# SCH_LED-Matrix-Halflife_2026-10-07.net
KiCad netlist of a schematic drawn in EasyEDA
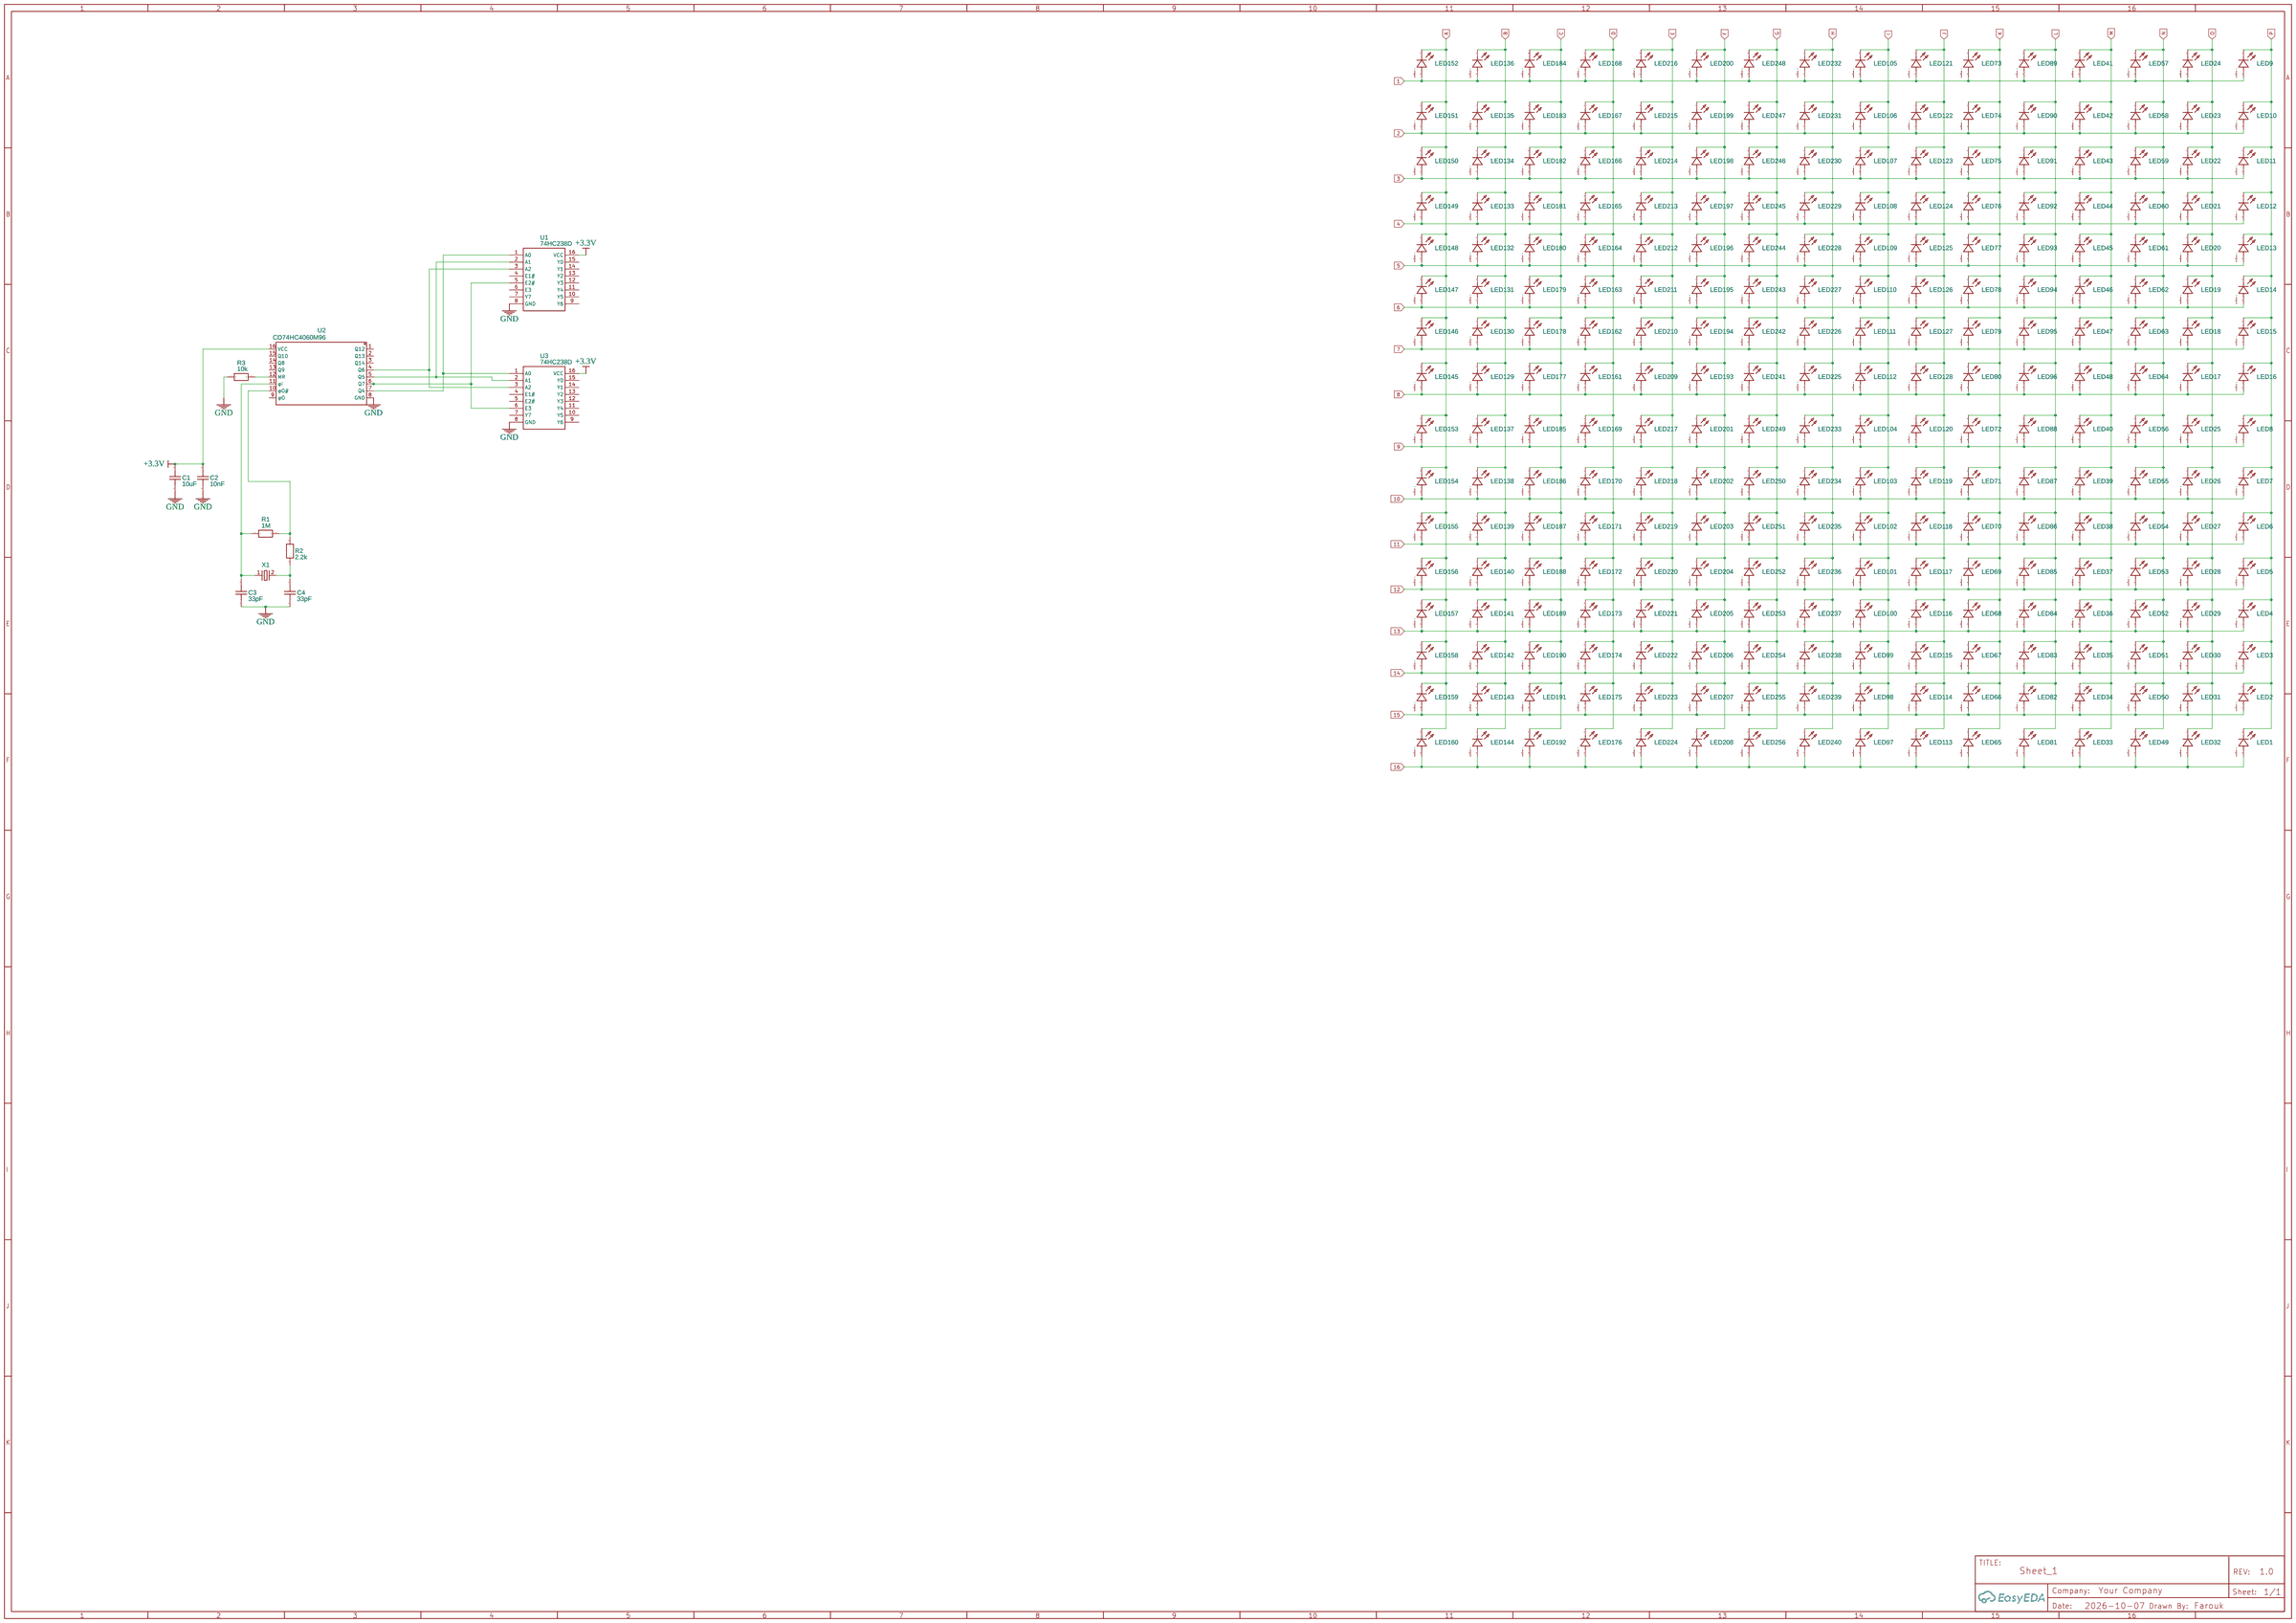
[diagram p0: schematic sheet]

(export (version "E")
  (design (tool "Eeschema 10.0.6"))
  (components
    (comp (ref "C1")
      (value "10uF")
      (fields
        (field (name "Manufacturer Part") "CC1210Y5V16V106ZN")
        (field (name "Manufacturer") "TORCH(火炬)")
      )
      (libsource (lib "") (part "CC1210Y5V16V106ZN"))
    )
    (comp (ref "C2")
      (value "10nF")
      (fields
        (field (name "Manufacturer Part") "CSA0805C0G103J500MT")
        (field (name "Manufacturer") "HRE(芯声)")
      )
      (libsource (lib "") (part "CSA0805C0G103J500MT"))
    )
    (comp (ref "C3")
      (value "33pF")
      (fields (field (name "Manufacturer Part") "600F330JT250XT") (field (name "Manufacturer") "Kyocera AVX"))
      (libsource (lib "") (part "600F330JT250XT"))
    )
    (comp (ref "C4")
      (value "33pF")
      (fields (field (name "Manufacturer Part") "600F330JT250XT") (field (name "Manufacturer") "Kyocera AVX"))
      (libsource (lib "") (part "600F330JT250XT"))
    )
    (comp (ref "LED1")
      (value "HL-A-5730D34WY-S1-08-CZ(LY)")
      (fields (field (name "Manufacturer") "HONGLITRONIC(鸿利光电)"))
      (libsource (lib "") (part "HL-A-5730D34WY-S1-08-CZ(LY)"))
    )
    (comp (ref "LED2")
      (value "HL-A-5730D34WY-S1-08-CZ(LY)")
      (fields (field (name "Manufacturer") "HONGLITRONIC(鸿利光电)"))
      (libsource (lib "") (part "HL-A-5730D34WY-S1-08-CZ(LY)"))
    )
    (comp (ref "LED3")
      (value "HL-A-5730D34WY-S1-08-CZ(LY)")
      (fields (field (name "Manufacturer") "HONGLITRONIC(鸿利光电)"))
      (libsource (lib "") (part "HL-A-5730D34WY-S1-08-CZ(LY)"))
    )
    (comp (ref "LED4")
      (value "HL-A-5730D34WY-S1-08-CZ(LY)")
      (fields (field (name "Manufacturer") "HONGLITRONIC(鸿利光电)"))
      (libsource (lib "") (part "HL-A-5730D34WY-S1-08-CZ(LY)"))
    )
    (comp (ref "LED5")
      (value "HL-A-5730D34WY-S1-08-CZ(LY)")
      (fields (field (name "Manufacturer") "HONGLITRONIC(鸿利光电)"))
      (libsource (lib "") (part "HL-A-5730D34WY-S1-08-CZ(LY)"))
    )
    (comp (ref "LED6")
      (value "HL-A-5730D34WY-S1-08-CZ(LY)")
      (fields (field (name "Manufacturer") "HONGLITRONIC(鸿利光电)"))
      (libsource (lib "") (part "HL-A-5730D34WY-S1-08-CZ(LY)"))
    )
    (comp (ref "LED7")
      (value "HL-A-5730D34WY-S1-08-CZ(LY)")
      (fields (field (name "Manufacturer") "HONGLITRONIC(鸿利光电)"))
      (libsource (lib "") (part "HL-A-5730D34WY-S1-08-CZ(LY)"))
    )
    (comp (ref "LED8")
      (value "HL-A-5730D34WY-S1-08-CZ(LY)")
      (fields (field (name "Manufacturer") "HONGLITRONIC(鸿利光电)"))
      (libsource (lib "") (part "HL-A-5730D34WY-S1-08-CZ(LY)"))
    )
    (comp (ref "LED9")
      (value "HL-A-5730D34WY-S1-08-CZ(LY)")
      (fields (field (name "Manufacturer") "HONGLITRONIC(鸿利光电)"))
      (libsource (lib "") (part "HL-A-5730D34WY-S1-08-CZ(LY)"))
    )
    (comp (ref "LED10")
      (value "HL-A-5730D34WY-S1-08-CZ(LY)")
      (fields (field (name "Manufacturer") "HONGLITRONIC(鸿利光电)"))
      (libsource (lib "") (part "HL-A-5730D34WY-S1-08-CZ(LY)"))
    )
    (comp (ref "LED11")
      (value "HL-A-5730D34WY-S1-08-CZ(LY)")
      (fields (field (name "Manufacturer") "HONGLITRONIC(鸿利光电)"))
      (libsource (lib "") (part "HL-A-5730D34WY-S1-08-CZ(LY)"))
    )
    (comp (ref "LED12")
      (value "HL-A-5730D34WY-S1-08-CZ(LY)")
      (fields (field (name "Manufacturer") "HONGLITRONIC(鸿利光电)"))
      (libsource (lib "") (part "HL-A-5730D34WY-S1-08-CZ(LY)"))
    )
    (comp (ref "LED13")
      (value "HL-A-5730D34WY-S1-08-CZ(LY)")
      (fields (field (name "Manufacturer") "HONGLITRONIC(鸿利光电)"))
      (libsource (lib "") (part "HL-A-5730D34WY-S1-08-CZ(LY)"))
    )
    (comp (ref "LED14")
      (value "HL-A-5730D34WY-S1-08-CZ(LY)")
      (fields (field (name "Manufacturer") "HONGLITRONIC(鸿利光电)"))
      (libsource (lib "") (part "HL-A-5730D34WY-S1-08-CZ(LY)"))
    )
    (comp (ref "LED15")
      (value "HL-A-5730D34WY-S1-08-CZ(LY)")
      (fields (field (name "Manufacturer") "HONGLITRONIC(鸿利光电)"))
      (libsource (lib "") (part "HL-A-5730D34WY-S1-08-CZ(LY)"))
    )
    (comp (ref "LED16")
      (value "HL-A-5730D34WY-S1-08-CZ(LY)")
      (fields (field (name "Manufacturer") "HONGLITRONIC(鸿利光电)"))
      (libsource (lib "") (part "HL-A-5730D34WY-S1-08-CZ(LY)"))
    )
    (comp (ref "LED17")
      (value "HL-A-5730D34WY-S1-08-CZ(LY)")
      (fields (field (name "Manufacturer") "HONGLITRONIC(鸿利光电)"))
      (libsource (lib "") (part "HL-A-5730D34WY-S1-08-CZ(LY)"))
    )
    (comp (ref "LED18")
      (value "HL-A-5730D34WY-S1-08-CZ(LY)")
      (fields (field (name "Manufacturer") "HONGLITRONIC(鸿利光电)"))
      (libsource (lib "") (part "HL-A-5730D34WY-S1-08-CZ(LY)"))
    )
    (comp (ref "LED19")
      (value "HL-A-5730D34WY-S1-08-CZ(LY)")
      (fields (field (name "Manufacturer") "HONGLITRONIC(鸿利光电)"))
      (libsource (lib "") (part "HL-A-5730D34WY-S1-08-CZ(LY)"))
    )
    (comp (ref "LED20")
      (value "HL-A-5730D34WY-S1-08-CZ(LY)")
      (fields (field (name "Manufacturer") "HONGLITRONIC(鸿利光电)"))
      (libsource (lib "") (part "HL-A-5730D34WY-S1-08-CZ(LY)"))
    )
    (comp (ref "LED21")
      (value "HL-A-5730D34WY-S1-08-CZ(LY)")
      (fields (field (name "Manufacturer") "HONGLITRONIC(鸿利光电)"))
      (libsource (lib "") (part "HL-A-5730D34WY-S1-08-CZ(LY)"))
    )
    (comp (ref "LED22")
      (value "HL-A-5730D34WY-S1-08-CZ(LY)")
      (fields (field (name "Manufacturer") "HONGLITRONIC(鸿利光电)"))
      (libsource (lib "") (part "HL-A-5730D34WY-S1-08-CZ(LY)"))
    )
    (comp (ref "LED23")
      (value "HL-A-5730D34WY-S1-08-CZ(LY)")
      (fields (field (name "Manufacturer") "HONGLITRONIC(鸿利光电)"))
      (libsource (lib "") (part "HL-A-5730D34WY-S1-08-CZ(LY)"))
    )
    (comp (ref "LED24")
      (value "HL-A-5730D34WY-S1-08-CZ(LY)")
      (fields (field (name "Manufacturer") "HONGLITRONIC(鸿利光电)"))
      (libsource (lib "") (part "HL-A-5730D34WY-S1-08-CZ(LY)"))
    )
    (comp (ref "LED25")
      (value "HL-A-5730D34WY-S1-08-CZ(LY)")
      (fields (field (name "Manufacturer") "HONGLITRONIC(鸿利光电)"))
      (libsource (lib "") (part "HL-A-5730D34WY-S1-08-CZ(LY)"))
    )
    (comp (ref "LED26")
      (value "HL-A-5730D34WY-S1-08-CZ(LY)")
      (fields (field (name "Manufacturer") "HONGLITRONIC(鸿利光电)"))
      (libsource (lib "") (part "HL-A-5730D34WY-S1-08-CZ(LY)"))
    )
    (comp (ref "LED27")
      (value "HL-A-5730D34WY-S1-08-CZ(LY)")
      (fields (field (name "Manufacturer") "HONGLITRONIC(鸿利光电)"))
      (libsource (lib "") (part "HL-A-5730D34WY-S1-08-CZ(LY)"))
    )
    (comp (ref "LED28")
      (value "HL-A-5730D34WY-S1-08-CZ(LY)")
      (fields (field (name "Manufacturer") "HONGLITRONIC(鸿利光电)"))
      (libsource (lib "") (part "HL-A-5730D34WY-S1-08-CZ(LY)"))
    )
    (comp (ref "LED29")
      (value "HL-A-5730D34WY-S1-08-CZ(LY)")
      (fields (field (name "Manufacturer") "HONGLITRONIC(鸿利光电)"))
      (libsource (lib "") (part "HL-A-5730D34WY-S1-08-CZ(LY)"))
    )
    (comp (ref "LED30")
      (value "HL-A-5730D34WY-S1-08-CZ(LY)")
      (fields (field (name "Manufacturer") "HONGLITRONIC(鸿利光电)"))
      (libsource (lib "") (part "HL-A-5730D34WY-S1-08-CZ(LY)"))
    )
    (comp (ref "LED31")
      (value "HL-A-5730D34WY-S1-08-CZ(LY)")
      (fields (field (name "Manufacturer") "HONGLITRONIC(鸿利光电)"))
      (libsource (lib "") (part "HL-A-5730D34WY-S1-08-CZ(LY)"))
    )
    (comp (ref "LED32")
      (value "HL-A-5730D34WY-S1-08-CZ(LY)")
      (fields (field (name "Manufacturer") "HONGLITRONIC(鸿利光电)"))
      (libsource (lib "") (part "HL-A-5730D34WY-S1-08-CZ(LY)"))
    )
    (comp (ref "LED33")
      (value "HL-A-5730D34WY-S1-08-CZ(LY)")
      (fields (field (name "Manufacturer") "HONGLITRONIC(鸿利光电)"))
      (libsource (lib "") (part "HL-A-5730D34WY-S1-08-CZ(LY)"))
    )
    (comp (ref "LED34")
      (value "HL-A-5730D34WY-S1-08-CZ(LY)")
      (fields (field (name "Manufacturer") "HONGLITRONIC(鸿利光电)"))
      (libsource (lib "") (part "HL-A-5730D34WY-S1-08-CZ(LY)"))
    )
    (comp (ref "LED35")
      (value "HL-A-5730D34WY-S1-08-CZ(LY)")
      (fields (field (name "Manufacturer") "HONGLITRONIC(鸿利光电)"))
      (libsource (lib "") (part "HL-A-5730D34WY-S1-08-CZ(LY)"))
    )
    (comp (ref "LED36")
      (value "HL-A-5730D34WY-S1-08-CZ(LY)")
      (fields (field (name "Manufacturer") "HONGLITRONIC(鸿利光电)"))
      (libsource (lib "") (part "HL-A-5730D34WY-S1-08-CZ(LY)"))
    )
    (comp (ref "LED37")
      (value "HL-A-5730D34WY-S1-08-CZ(LY)")
      (fields (field (name "Manufacturer") "HONGLITRONIC(鸿利光电)"))
      (libsource (lib "") (part "HL-A-5730D34WY-S1-08-CZ(LY)"))
    )
    (comp (ref "LED38")
      (value "HL-A-5730D34WY-S1-08-CZ(LY)")
      (fields (field (name "Manufacturer") "HONGLITRONIC(鸿利光电)"))
      (libsource (lib "") (part "HL-A-5730D34WY-S1-08-CZ(LY)"))
    )
    (comp (ref "LED39")
      (value "HL-A-5730D34WY-S1-08-CZ(LY)")
      (fields (field (name "Manufacturer") "HONGLITRONIC(鸿利光电)"))
      (libsource (lib "") (part "HL-A-5730D34WY-S1-08-CZ(LY)"))
    )
    (comp (ref "LED40")
      (value "HL-A-5730D34WY-S1-08-CZ(LY)")
      (fields (field (name "Manufacturer") "HONGLITRONIC(鸿利光电)"))
      (libsource (lib "") (part "HL-A-5730D34WY-S1-08-CZ(LY)"))
    )
    (comp (ref "LED41")
      (value "HL-A-5730D34WY-S1-08-CZ(LY)")
      (fields (field (name "Manufacturer") "HONGLITRONIC(鸿利光电)"))
      (libsource (lib "") (part "HL-A-5730D34WY-S1-08-CZ(LY)"))
    )
    (comp (ref "LED42")
      (value "HL-A-5730D34WY-S1-08-CZ(LY)")
      (fields (field (name "Manufacturer") "HONGLITRONIC(鸿利光电)"))
      (libsource (lib "") (part "HL-A-5730D34WY-S1-08-CZ(LY)"))
    )
    (comp (ref "LED43")
      (value "HL-A-5730D34WY-S1-08-CZ(LY)")
      (fields (field (name "Manufacturer") "HONGLITRONIC(鸿利光电)"))
      (libsource (lib "") (part "HL-A-5730D34WY-S1-08-CZ(LY)"))
    )
    (comp (ref "LED44")
      (value "HL-A-5730D34WY-S1-08-CZ(LY)")
      (fields (field (name "Manufacturer") "HONGLITRONIC(鸿利光电)"))
      (libsource (lib "") (part "HL-A-5730D34WY-S1-08-CZ(LY)"))
    )
    (comp (ref "LED45")
      (value "HL-A-5730D34WY-S1-08-CZ(LY)")
      (fields (field (name "Manufacturer") "HONGLITRONIC(鸿利光电)"))
      (libsource (lib "") (part "HL-A-5730D34WY-S1-08-CZ(LY)"))
    )
    (comp (ref "LED46")
      (value "HL-A-5730D34WY-S1-08-CZ(LY)")
      (fields (field (name "Manufacturer") "HONGLITRONIC(鸿利光电)"))
      (libsource (lib "") (part "HL-A-5730D34WY-S1-08-CZ(LY)"))
    )
    (comp (ref "LED47")
      (value "HL-A-5730D34WY-S1-08-CZ(LY)")
      (fields (field (name "Manufacturer") "HONGLITRONIC(鸿利光电)"))
      (libsource (lib "") (part "HL-A-5730D34WY-S1-08-CZ(LY)"))
    )
    (comp (ref "LED48")
      (value "HL-A-5730D34WY-S1-08-CZ(LY)")
      (fields (field (name "Manufacturer") "HONGLITRONIC(鸿利光电)"))
      (libsource (lib "") (part "HL-A-5730D34WY-S1-08-CZ(LY)"))
    )
    (comp (ref "LED49")
      (value "HL-A-5730D34WY-S1-08-CZ(LY)")
      (fields (field (name "Manufacturer") "HONGLITRONIC(鸿利光电)"))
      (libsource (lib "") (part "HL-A-5730D34WY-S1-08-CZ(LY)"))
    )
    (comp (ref "LED50")
      (value "HL-A-5730D34WY-S1-08-CZ(LY)")
      (fields (field (name "Manufacturer") "HONGLITRONIC(鸿利光电)"))
      (libsource (lib "") (part "HL-A-5730D34WY-S1-08-CZ(LY)"))
    )
    (comp (ref "LED51")
      (value "HL-A-5730D34WY-S1-08-CZ(LY)")
      (fields (field (name "Manufacturer") "HONGLITRONIC(鸿利光电)"))
      (libsource (lib "") (part "HL-A-5730D34WY-S1-08-CZ(LY)"))
    )
    (comp (ref "LED52")
      (value "HL-A-5730D34WY-S1-08-CZ(LY)")
      (fields (field (name "Manufacturer") "HONGLITRONIC(鸿利光电)"))
      (libsource (lib "") (part "HL-A-5730D34WY-S1-08-CZ(LY)"))
    )
    (comp (ref "LED53")
      (value "HL-A-5730D34WY-S1-08-CZ(LY)")
      (fields (field (name "Manufacturer") "HONGLITRONIC(鸿利光电)"))
      (libsource (lib "") (part "HL-A-5730D34WY-S1-08-CZ(LY)"))
    )
    (comp (ref "LED54")
      (value "HL-A-5730D34WY-S1-08-CZ(LY)")
      (fields (field (name "Manufacturer") "HONGLITRONIC(鸿利光电)"))
      (libsource (lib "") (part "HL-A-5730D34WY-S1-08-CZ(LY)"))
    )
    (comp (ref "LED55")
      (value "HL-A-5730D34WY-S1-08-CZ(LY)")
      (fields (field (name "Manufacturer") "HONGLITRONIC(鸿利光电)"))
      (libsource (lib "") (part "HL-A-5730D34WY-S1-08-CZ(LY)"))
    )
    (comp (ref "LED56")
      (value "HL-A-5730D34WY-S1-08-CZ(LY)")
      (fields (field (name "Manufacturer") "HONGLITRONIC(鸿利光电)"))
      (libsource (lib "") (part "HL-A-5730D34WY-S1-08-CZ(LY)"))
    )
    (comp (ref "LED57")
      (value "HL-A-5730D34WY-S1-08-CZ(LY)")
      (fields (field (name "Manufacturer") "HONGLITRONIC(鸿利光电)"))
      (libsource (lib "") (part "HL-A-5730D34WY-S1-08-CZ(LY)"))
    )
    (comp (ref "LED58")
      (value "HL-A-5730D34WY-S1-08-CZ(LY)")
      (fields (field (name "Manufacturer") "HONGLITRONIC(鸿利光电)"))
      (libsource (lib "") (part "HL-A-5730D34WY-S1-08-CZ(LY)"))
    )
    (comp (ref "LED59")
      (value "HL-A-5730D34WY-S1-08-CZ(LY)")
      (fields (field (name "Manufacturer") "HONGLITRONIC(鸿利光电)"))
      (libsource (lib "") (part "HL-A-5730D34WY-S1-08-CZ(LY)"))
    )
    (comp (ref "LED60")
      (value "HL-A-5730D34WY-S1-08-CZ(LY)")
      (fields (field (name "Manufacturer") "HONGLITRONIC(鸿利光电)"))
      (libsource (lib "") (part "HL-A-5730D34WY-S1-08-CZ(LY)"))
    )
    (comp (ref "LED61")
      (value "HL-A-5730D34WY-S1-08-CZ(LY)")
      (fields (field (name "Manufacturer") "HONGLITRONIC(鸿利光电)"))
      (libsource (lib "") (part "HL-A-5730D34WY-S1-08-CZ(LY)"))
    )
    (comp (ref "LED62")
      (value "HL-A-5730D34WY-S1-08-CZ(LY)")
      (fields (field (name "Manufacturer") "HONGLITRONIC(鸿利光电)"))
      (libsource (lib "") (part "HL-A-5730D34WY-S1-08-CZ(LY)"))
    )
    (comp (ref "LED63")
      (value "HL-A-5730D34WY-S1-08-CZ(LY)")
      (fields (field (name "Manufacturer") "HONGLITRONIC(鸿利光电)"))
      (libsource (lib "") (part "HL-A-5730D34WY-S1-08-CZ(LY)"))
    )
    (comp (ref "LED64")
      (value "HL-A-5730D34WY-S1-08-CZ(LY)")
      (fields (field (name "Manufacturer") "HONGLITRONIC(鸿利光电)"))
      (libsource (lib "") (part "HL-A-5730D34WY-S1-08-CZ(LY)"))
    )
    (comp (ref "LED65")
      (value "HL-A-5730D34WY-S1-08-CZ(LY)")
      (fields (field (name "Manufacturer") "HONGLITRONIC(鸿利光电)"))
      (libsource (lib "") (part "HL-A-5730D34WY-S1-08-CZ(LY)"))
    )
    (comp (ref "LED66")
      (value "HL-A-5730D34WY-S1-08-CZ(LY)")
      (fields (field (name "Manufacturer") "HONGLITRONIC(鸿利光电)"))
      (libsource (lib "") (part "HL-A-5730D34WY-S1-08-CZ(LY)"))
    )
    (comp (ref "LED67")
      (value "HL-A-5730D34WY-S1-08-CZ(LY)")
      (fields (field (name "Manufacturer") "HONGLITRONIC(鸿利光电)"))
      (libsource (lib "") (part "HL-A-5730D34WY-S1-08-CZ(LY)"))
    )
    (comp (ref "LED68")
      (value "HL-A-5730D34WY-S1-08-CZ(LY)")
      (fields (field (name "Manufacturer") "HONGLITRONIC(鸿利光电)"))
      (libsource (lib "") (part "HL-A-5730D34WY-S1-08-CZ(LY)"))
    )
    (comp (ref "LED69")
      (value "HL-A-5730D34WY-S1-08-CZ(LY)")
      (fields (field (name "Manufacturer") "HONGLITRONIC(鸿利光电)"))
      (libsource (lib "") (part "HL-A-5730D34WY-S1-08-CZ(LY)"))
    )
    (comp (ref "LED70")
      (value "HL-A-5730D34WY-S1-08-CZ(LY)")
      (fields (field (name "Manufacturer") "HONGLITRONIC(鸿利光电)"))
      (libsource (lib "") (part "HL-A-5730D34WY-S1-08-CZ(LY)"))
    )
    (comp (ref "LED71")
      (value "HL-A-5730D34WY-S1-08-CZ(LY)")
      (fields (field (name "Manufacturer") "HONGLITRONIC(鸿利光电)"))
      (libsource (lib "") (part "HL-A-5730D34WY-S1-08-CZ(LY)"))
    )
    (comp (ref "LED72")
      (value "HL-A-5730D34WY-S1-08-CZ(LY)")
      (fields (field (name "Manufacturer") "HONGLITRONIC(鸿利光电)"))
      (libsource (lib "") (part "HL-A-5730D34WY-S1-08-CZ(LY)"))
    )
    (comp (ref "LED73")
      (value "HL-A-5730D34WY-S1-08-CZ(LY)")
      (fields (field (name "Manufacturer") "HONGLITRONIC(鸿利光电)"))
      (libsource (lib "") (part "HL-A-5730D34WY-S1-08-CZ(LY)"))
    )
    (comp (ref "LED74")
      (value "HL-A-5730D34WY-S1-08-CZ(LY)")
      (fields (field (name "Manufacturer") "HONGLITRONIC(鸿利光电)"))
      (libsource (lib "") (part "HL-A-5730D34WY-S1-08-CZ(LY)"))
    )
    (comp (ref "LED75")
      (value "HL-A-5730D34WY-S1-08-CZ(LY)")
      (fields (field (name "Manufacturer") "HONGLITRONIC(鸿利光电)"))
      (libsource (lib "") (part "HL-A-5730D34WY-S1-08-CZ(LY)"))
    )
    (comp (ref "LED76")
      (value "HL-A-5730D34WY-S1-08-CZ(LY)")
      (fields (field (name "Manufacturer") "HONGLITRONIC(鸿利光电)"))
      (libsource (lib "") (part "HL-A-5730D34WY-S1-08-CZ(LY)"))
    )
    (comp (ref "LED77")
      (value "HL-A-5730D34WY-S1-08-CZ(LY)")
      (fields (field (name "Manufacturer") "HONGLITRONIC(鸿利光电)"))
      (libsource (lib "") (part "HL-A-5730D34WY-S1-08-CZ(LY)"))
    )
    (comp (ref "LED78")
      (value "HL-A-5730D34WY-S1-08-CZ(LY)")
      (fields (field (name "Manufacturer") "HONGLITRONIC(鸿利光电)"))
      (libsource (lib "") (part "HL-A-5730D34WY-S1-08-CZ(LY)"))
    )
    (comp (ref "LED79")
      (value "HL-A-5730D34WY-S1-08-CZ(LY)")
      (fields (field (name "Manufacturer") "HONGLITRONIC(鸿利光电)"))
      (libsource (lib "") (part "HL-A-5730D34WY-S1-08-CZ(LY)"))
    )
    (comp (ref "LED80")
      (value "HL-A-5730D34WY-S1-08-CZ(LY)")
      (fields (field (name "Manufacturer") "HONGLITRONIC(鸿利光电)"))
      (libsource (lib "") (part "HL-A-5730D34WY-S1-08-CZ(LY)"))
    )
    (comp (ref "LED81")
      (value "HL-A-5730D34WY-S1-08-CZ(LY)")
      (fields (field (name "Manufacturer") "HONGLITRONIC(鸿利光电)"))
      (libsource (lib "") (part "HL-A-5730D34WY-S1-08-CZ(LY)"))
    )
    (comp (ref "LED82")
      (value "HL-A-5730D34WY-S1-08-CZ(LY)")
      (fields (field (name "Manufacturer") "HONGLITRONIC(鸿利光电)"))
      (libsource (lib "") (part "HL-A-5730D34WY-S1-08-CZ(LY)"))
    )
    (comp (ref "LED83")
      (value "HL-A-5730D34WY-S1-08-CZ(LY)")
      (fields (field (name "Manufacturer") "HONGLITRONIC(鸿利光电)"))
      (libsource (lib "") (part "HL-A-5730D34WY-S1-08-CZ(LY)"))
    )
    (comp (ref "LED84")
      (value "HL-A-5730D34WY-S1-08-CZ(LY)")
      (fields (field (name "Manufacturer") "HONGLITRONIC(鸿利光电)"))
      (libsource (lib "") (part "HL-A-5730D34WY-S1-08-CZ(LY)"))
    )
    (comp (ref "LED85")
      (value "HL-A-5730D34WY-S1-08-CZ(LY)")
      (fields (field (name "Manufacturer") "HONGLITRONIC(鸿利光电)"))
      (libsource (lib "") (part "HL-A-5730D34WY-S1-08-CZ(LY)"))
    )
    (comp (ref "LED86")
      (value "HL-A-5730D34WY-S1-08-CZ(LY)")
      (fields (field (name "Manufacturer") "HONGLITRONIC(鸿利光电)"))
      (libsource (lib "") (part "HL-A-5730D34WY-S1-08-CZ(LY)"))
    )
    (comp (ref "LED87")
      (value "HL-A-5730D34WY-S1-08-CZ(LY)")
      (fields (field (name "Manufacturer") "HONGLITRONIC(鸿利光电)"))
      (libsource (lib "") (part "HL-A-5730D34WY-S1-08-CZ(LY)"))
    )
    (comp (ref "LED88")
      (value "HL-A-5730D34WY-S1-08-CZ(LY)")
      (fields (field (name "Manufacturer") "HONGLITRONIC(鸿利光电)"))
      (libsource (lib "") (part "HL-A-5730D34WY-S1-08-CZ(LY)"))
    )
    (comp (ref "LED89")
      (value "HL-A-5730D34WY-S1-08-CZ(LY)")
      (fields (field (name "Manufacturer") "HONGLITRONIC(鸿利光电)"))
      (libsource (lib "") (part "HL-A-5730D34WY-S1-08-CZ(LY)"))
    )
    (comp (ref "LED90")
      (value "HL-A-5730D34WY-S1-08-CZ(LY)")
      (fields (field (name "Manufacturer") "HONGLITRONIC(鸿利光电)"))
      (libsource (lib "") (part "HL-A-5730D34WY-S1-08-CZ(LY)"))
    )
    (comp (ref "LED91")
      (value "HL-A-5730D34WY-S1-08-CZ(LY)")
      (fields (field (name "Manufacturer") "HONGLITRONIC(鸿利光电)"))
      (libsource (lib "") (part "HL-A-5730D34WY-S1-08-CZ(LY)"))
    )
    (comp (ref "LED92")
      (value "HL-A-5730D34WY-S1-08-CZ(LY)")
      (fields (field (name "Manufacturer") "HONGLITRONIC(鸿利光电)"))
      (libsource (lib "") (part "HL-A-5730D34WY-S1-08-CZ(LY)"))
    )
    (comp (ref "LED93")
      (value "HL-A-5730D34WY-S1-08-CZ(LY)")
      (fields (field (name "Manufacturer") "HONGLITRONIC(鸿利光电)"))
      (libsource (lib "") (part "HL-A-5730D34WY-S1-08-CZ(LY)"))
    )
    (comp (ref "LED94")
      (value "HL-A-5730D34WY-S1-08-CZ(LY)")
      (fields (field (name "Manufacturer") "HONGLITRONIC(鸿利光电)"))
      (libsource (lib "") (part "HL-A-5730D34WY-S1-08-CZ(LY)"))
    )
    (comp (ref "LED95")
      (value "HL-A-5730D34WY-S1-08-CZ(LY)")
      (fields (field (name "Manufacturer") "HONGLITRONIC(鸿利光电)"))
      (libsource (lib "") (part "HL-A-5730D34WY-S1-08-CZ(LY)"))
    )
    (comp (ref "LED96")
      (value "HL-A-5730D34WY-S1-08-CZ(LY)")
      (fields (field (name "Manufacturer") "HONGLITRONIC(鸿利光电)"))
      (libsource (lib "") (part "HL-A-5730D34WY-S1-08-CZ(LY)"))
    )
    (comp (ref "LED97")
      (value "HL-A-5730D34WY-S1-08-CZ(LY)")
      (fields (field (name "Manufacturer") "HONGLITRONIC(鸿利光电)"))
      (libsource (lib "") (part "HL-A-5730D34WY-S1-08-CZ(LY)"))
    )
    (comp (ref "LED98")
      (value "HL-A-5730D34WY-S1-08-CZ(LY)")
      (fields (field (name "Manufacturer") "HONGLITRONIC(鸿利光电)"))
      (libsource (lib "") (part "HL-A-5730D34WY-S1-08-CZ(LY)"))
    )
    (comp (ref "LED99")
      (value "HL-A-5730D34WY-S1-08-CZ(LY)")
      (fields (field (name "Manufacturer") "HONGLITRONIC(鸿利光电)"))
      (libsource (lib "") (part "HL-A-5730D34WY-S1-08-CZ(LY)"))
    )
    (comp (ref "LED100")
      (value "HL-A-5730D34WY-S1-08-CZ(LY)")
      (fields (field (name "Manufacturer") "HONGLITRONIC(鸿利光电)"))
      (libsource (lib "") (part "HL-A-5730D34WY-S1-08-CZ(LY)"))
    )
    (comp (ref "LED101")
      (value "HL-A-5730D34WY-S1-08-CZ(LY)")
      (fields (field (name "Manufacturer") "HONGLITRONIC(鸿利光电)"))
      (libsource (lib "") (part "HL-A-5730D34WY-S1-08-CZ(LY)"))
    )
    (comp (ref "LED102")
      (value "HL-A-5730D34WY-S1-08-CZ(LY)")
      (fields (field (name "Manufacturer") "HONGLITRONIC(鸿利光电)"))
      (libsource (lib "") (part "HL-A-5730D34WY-S1-08-CZ(LY)"))
    )
    (comp (ref "LED103")
      (value "HL-A-5730D34WY-S1-08-CZ(LY)")
      (fields (field (name "Manufacturer") "HONGLITRONIC(鸿利光电)"))
      (libsource (lib "") (part "HL-A-5730D34WY-S1-08-CZ(LY)"))
    )
    (comp (ref "LED104")
      (value "HL-A-5730D34WY-S1-08-CZ(LY)")
      (fields (field (name "Manufacturer") "HONGLITRONIC(鸿利光电)"))
      (libsource (lib "") (part "HL-A-5730D34WY-S1-08-CZ(LY)"))
    )
    (comp (ref "LED105")
      (value "HL-A-5730D34WY-S1-08-CZ(LY)")
      (fields (field (name "Manufacturer") "HONGLITRONIC(鸿利光电)"))
      (libsource (lib "") (part "HL-A-5730D34WY-S1-08-CZ(LY)"))
    )
    (comp (ref "LED106")
      (value "HL-A-5730D34WY-S1-08-CZ(LY)")
      (fields (field (name "Manufacturer") "HONGLITRONIC(鸿利光电)"))
      (libsource (lib "") (part "HL-A-5730D34WY-S1-08-CZ(LY)"))
    )
    (comp (ref "LED107")
      (value "HL-A-5730D34WY-S1-08-CZ(LY)")
      (fields (field (name "Manufacturer") "HONGLITRONIC(鸿利光电)"))
      (libsource (lib "") (part "HL-A-5730D34WY-S1-08-CZ(LY)"))
    )
    (comp (ref "LED108")
      (value "HL-A-5730D34WY-S1-08-CZ(LY)")
      (fields (field (name "Manufacturer") "HONGLITRONIC(鸿利光电)"))
      (libsource (lib "") (part "HL-A-5730D34WY-S1-08-CZ(LY)"))
    )
    (comp (ref "LED109")
      (value "HL-A-5730D34WY-S1-08-CZ(LY)")
      (fields (field (name "Manufacturer") "HONGLITRONIC(鸿利光电)"))
      (libsource (lib "") (part "HL-A-5730D34WY-S1-08-CZ(LY)"))
    )
    (comp (ref "LED110")
      (value "HL-A-5730D34WY-S1-08-CZ(LY)")
      (fields (field (name "Manufacturer") "HONGLITRONIC(鸿利光电)"))
      (libsource (lib "") (part "HL-A-5730D34WY-S1-08-CZ(LY)"))
    )
    (comp (ref "LED111")
      (value "HL-A-5730D34WY-S1-08-CZ(LY)")
      (fields (field (name "Manufacturer") "HONGLITRONIC(鸿利光电)"))
      (libsource (lib "") (part "HL-A-5730D34WY-S1-08-CZ(LY)"))
    )
    (comp (ref "LED112")
      (value "HL-A-5730D34WY-S1-08-CZ(LY)")
      (fields (field (name "Manufacturer") "HONGLITRONIC(鸿利光电)"))
      (libsource (lib "") (part "HL-A-5730D34WY-S1-08-CZ(LY)"))
    )
    (comp (ref "LED113")
      (value "HL-A-5730D34WY-S1-08-CZ(LY)")
      (fields (field (name "Manufacturer") "HONGLITRONIC(鸿利光电)"))
      (libsource (lib "") (part "HL-A-5730D34WY-S1-08-CZ(LY)"))
    )
    (comp (ref "LED114")
      (value "HL-A-5730D34WY-S1-08-CZ(LY)")
      (fields (field (name "Manufacturer") "HONGLITRONIC(鸿利光电)"))
      (libsource (lib "") (part "HL-A-5730D34WY-S1-08-CZ(LY)"))
    )
    (comp (ref "LED115")
      (value "HL-A-5730D34WY-S1-08-CZ(LY)")
      (fields (field (name "Manufacturer") "HONGLITRONIC(鸿利光电)"))
      (libsource (lib "") (part "HL-A-5730D34WY-S1-08-CZ(LY)"))
    )
    (comp (ref "LED116")
      (value "HL-A-5730D34WY-S1-08-CZ(LY)")
      (fields (field (name "Manufacturer") "HONGLITRONIC(鸿利光电)"))
      (libsource (lib "") (part "HL-A-5730D34WY-S1-08-CZ(LY)"))
    )
    (comp (ref "LED117")
      (value "HL-A-5730D34WY-S1-08-CZ(LY)")
      (fields (field (name "Manufacturer") "HONGLITRONIC(鸿利光电)"))
      (libsource (lib "") (part "HL-A-5730D34WY-S1-08-CZ(LY)"))
    )
    (comp (ref "LED118")
      (value "HL-A-5730D34WY-S1-08-CZ(LY)")
      (fields (field (name "Manufacturer") "HONGLITRONIC(鸿利光电)"))
      (libsource (lib "") (part "HL-A-5730D34WY-S1-08-CZ(LY)"))
    )
    (comp (ref "LED119")
      (value "HL-A-5730D34WY-S1-08-CZ(LY)")
      (fields (field (name "Manufacturer") "HONGLITRONIC(鸿利光电)"))
      (libsource (lib "") (part "HL-A-5730D34WY-S1-08-CZ(LY)"))
    )
    (comp (ref "LED120")
      (value "HL-A-5730D34WY-S1-08-CZ(LY)")
      (fields (field (name "Manufacturer") "HONGLITRONIC(鸿利光电)"))
      (libsource (lib "") (part "HL-A-5730D34WY-S1-08-CZ(LY)"))
    )
    (comp (ref "LED121")
      (value "HL-A-5730D34WY-S1-08-CZ(LY)")
      (fields (field (name "Manufacturer") "HONGLITRONIC(鸿利光电)"))
      (libsource (lib "") (part "HL-A-5730D34WY-S1-08-CZ(LY)"))
    )
    (comp (ref "LED122")
      (value "HL-A-5730D34WY-S1-08-CZ(LY)")
      (fields (field (name "Manufacturer") "HONGLITRONIC(鸿利光电)"))
      (libsource (lib "") (part "HL-A-5730D34WY-S1-08-CZ(LY)"))
    )
    (comp (ref "LED123")
      (value "HL-A-5730D34WY-S1-08-CZ(LY)")
      (fields (field (name "Manufacturer") "HONGLITRONIC(鸿利光电)"))
      (libsource (lib "") (part "HL-A-5730D34WY-S1-08-CZ(LY)"))
    )
    (comp (ref "LED124")
      (value "HL-A-5730D34WY-S1-08-CZ(LY)")
      (fields (field (name "Manufacturer") "HONGLITRONIC(鸿利光电)"))
      (libsource (lib "") (part "HL-A-5730D34WY-S1-08-CZ(LY)"))
    )
    (comp (ref "LED125")
      (value "HL-A-5730D34WY-S1-08-CZ(LY)")
      (fields (field (name "Manufacturer") "HONGLITRONIC(鸿利光电)"))
      (libsource (lib "") (part "HL-A-5730D34WY-S1-08-CZ(LY)"))
    )
    (comp (ref "LED126")
      (value "HL-A-5730D34WY-S1-08-CZ(LY)")
      (fields (field (name "Manufacturer") "HONGLITRONIC(鸿利光电)"))
      (libsource (lib "") (part "HL-A-5730D34WY-S1-08-CZ(LY)"))
    )
    (comp (ref "LED127")
      (value "HL-A-5730D34WY-S1-08-CZ(LY)")
      (fields (field (name "Manufacturer") "HONGLITRONIC(鸿利光电)"))
      (libsource (lib "") (part "HL-A-5730D34WY-S1-08-CZ(LY)"))
    )
    (comp (ref "LED128")
      (value "HL-A-5730D34WY-S1-08-CZ(LY)")
      (fields (field (name "Manufacturer") "HONGLITRONIC(鸿利光电)"))
      (libsource (lib "") (part "HL-A-5730D34WY-S1-08-CZ(LY)"))
    )
    (comp (ref "LED129")
      (value "HL-A-5730D34WY-S1-08-CZ(LY)")
      (fields (field (name "Manufacturer") "HONGLITRONIC(鸿利光电)"))
      (libsource (lib "") (part "HL-A-5730D34WY-S1-08-CZ(LY)"))
    )
    (comp (ref "LED130")
      (value "HL-A-5730D34WY-S1-08-CZ(LY)")
      (fields (field (name "Manufacturer") "HONGLITRONIC(鸿利光电)"))
      (libsource (lib "") (part "HL-A-5730D34WY-S1-08-CZ(LY)"))
    )
    (comp (ref "LED131")
      (value "HL-A-5730D34WY-S1-08-CZ(LY)")
      (fields (field (name "Manufacturer") "HONGLITRONIC(鸿利光电)"))
      (libsource (lib "") (part "HL-A-5730D34WY-S1-08-CZ(LY)"))
    )
    (comp (ref "LED132")
      (value "HL-A-5730D34WY-S1-08-CZ(LY)")
      (fields (field (name "Manufacturer") "HONGLITRONIC(鸿利光电)"))
      (libsource (lib "") (part "HL-A-5730D34WY-S1-08-CZ(LY)"))
    )
    (comp (ref "LED133")
      (value "HL-A-5730D34WY-S1-08-CZ(LY)")
      (fields (field (name "Manufacturer") "HONGLITRONIC(鸿利光电)"))
      (libsource (lib "") (part "HL-A-5730D34WY-S1-08-CZ(LY)"))
    )
    (comp (ref "LED134")
      (value "HL-A-5730D34WY-S1-08-CZ(LY)")
      (fields (field (name "Manufacturer") "HONGLITRONIC(鸿利光电)"))
      (libsource (lib "") (part "HL-A-5730D34WY-S1-08-CZ(LY)"))
    )
    (comp (ref "LED135")
      (value "HL-A-5730D34WY-S1-08-CZ(LY)")
      (fields (field (name "Manufacturer") "HONGLITRONIC(鸿利光电)"))
      (libsource (lib "") (part "HL-A-5730D34WY-S1-08-CZ(LY)"))
    )
    (comp (ref "LED136")
      (value "HL-A-5730D34WY-S1-08-CZ(LY)")
      (fields (field (name "Manufacturer") "HONGLITRONIC(鸿利光电)"))
      (libsource (lib "") (part "HL-A-5730D34WY-S1-08-CZ(LY)"))
    )
    (comp (ref "LED137")
      (value "HL-A-5730D34WY-S1-08-CZ(LY)")
      (fields (field (name "Manufacturer") "HONGLITRONIC(鸿利光电)"))
      (libsource (lib "") (part "HL-A-5730D34WY-S1-08-CZ(LY)"))
    )
    (comp (ref "LED138")
      (value "HL-A-5730D34WY-S1-08-CZ(LY)")
      (fields (field (name "Manufacturer") "HONGLITRONIC(鸿利光电)"))
      (libsource (lib "") (part "HL-A-5730D34WY-S1-08-CZ(LY)"))
    )
    (comp (ref "LED139")
      (value "HL-A-5730D34WY-S1-08-CZ(LY)")
      (fields (field (name "Manufacturer") "HONGLITRONIC(鸿利光电)"))
      (libsource (lib "") (part "HL-A-5730D34WY-S1-08-CZ(LY)"))
    )
    (comp (ref "LED140")
      (value "HL-A-5730D34WY-S1-08-CZ(LY)")
      (fields (field (name "Manufacturer") "HONGLITRONIC(鸿利光电)"))
      (libsource (lib "") (part "HL-A-5730D34WY-S1-08-CZ(LY)"))
    )
    (comp (ref "LED141")
      (value "HL-A-5730D34WY-S1-08-CZ(LY)")
      (fields (field (name "Manufacturer") "HONGLITRONIC(鸿利光电)"))
      (libsource (lib "") (part "HL-A-5730D34WY-S1-08-CZ(LY)"))
    )
    (comp (ref "LED142")
      (value "HL-A-5730D34WY-S1-08-CZ(LY)")
      (fields (field (name "Manufacturer") "HONGLITRONIC(鸿利光电)"))
      (libsource (lib "") (part "HL-A-5730D34WY-S1-08-CZ(LY)"))
    )
    (comp (ref "LED143")
      (value "HL-A-5730D34WY-S1-08-CZ(LY)")
      (fields (field (name "Manufacturer") "HONGLITRONIC(鸿利光电)"))
      (libsource (lib "") (part "HL-A-5730D34WY-S1-08-CZ(LY)"))
    )
    (comp (ref "LED144")
      (value "HL-A-5730D34WY-S1-08-CZ(LY)")
      (fields (field (name "Manufacturer") "HONGLITRONIC(鸿利光电)"))
      (libsource (lib "") (part "HL-A-5730D34WY-S1-08-CZ(LY)"))
    )
    (comp (ref "LED145")
      (value "HL-A-5730D34WY-S1-08-CZ(LY)")
      (fields (field (name "Manufacturer") "HONGLITRONIC(鸿利光电)"))
      (libsource (lib "") (part "HL-A-5730D34WY-S1-08-CZ(LY)"))
    )
    (comp (ref "LED146")
      (value "HL-A-5730D34WY-S1-08-CZ(LY)")
      (fields (field (name "Manufacturer") "HONGLITRONIC(鸿利光电)"))
      (libsource (lib "") (part "HL-A-5730D34WY-S1-08-CZ(LY)"))
    )
    (comp (ref "LED147")
      (value "HL-A-5730D34WY-S1-08-CZ(LY)")
      (fields (field (name "Manufacturer") "HONGLITRONIC(鸿利光电)"))
      (libsource (lib "") (part "HL-A-5730D34WY-S1-08-CZ(LY)"))
    )
    (comp (ref "LED148")
      (value "HL-A-5730D34WY-S1-08-CZ(LY)")
      (fields (field (name "Manufacturer") "HONGLITRONIC(鸿利光电)"))
      (libsource (lib "") (part "HL-A-5730D34WY-S1-08-CZ(LY)"))
    )
    (comp (ref "LED149")
      (value "HL-A-5730D34WY-S1-08-CZ(LY)")
      (fields (field (name "Manufacturer") "HONGLITRONIC(鸿利光电)"))
      (libsource (lib "") (part "HL-A-5730D34WY-S1-08-CZ(LY)"))
    )
    (comp (ref "LED150")
      (value "HL-A-5730D34WY-S1-08-CZ(LY)")
      (fields (field (name "Manufacturer") "HONGLITRONIC(鸿利光电)"))
      (libsource (lib "") (part "HL-A-5730D34WY-S1-08-CZ(LY)"))
    )
    (comp (ref "LED151")
      (value "HL-A-5730D34WY-S1-08-CZ(LY)")
      (fields (field (name "Manufacturer") "HONGLITRONIC(鸿利光电)"))
      (libsource (lib "") (part "HL-A-5730D34WY-S1-08-CZ(LY)"))
    )
    (comp (ref "LED152")
      (value "HL-A-5730D34WY-S1-08-CZ(LY)")
      (fields (field (name "Manufacturer") "HONGLITRONIC(鸿利光电)"))
      (libsource (lib "") (part "HL-A-5730D34WY-S1-08-CZ(LY)"))
    )
    (comp (ref "LED153")
      (value "HL-A-5730D34WY-S1-08-CZ(LY)")
      (fields (field (name "Manufacturer") "HONGLITRONIC(鸿利光电)"))
      (libsource (lib "") (part "HL-A-5730D34WY-S1-08-CZ(LY)"))
    )
    (comp (ref "LED154")
      (value "HL-A-5730D34WY-S1-08-CZ(LY)")
      (fields (field (name "Manufacturer") "HONGLITRONIC(鸿利光电)"))
      (libsource (lib "") (part "HL-A-5730D34WY-S1-08-CZ(LY)"))
    )
    (comp (ref "LED155")
      (value "HL-A-5730D34WY-S1-08-CZ(LY)")
      (fields (field (name "Manufacturer") "HONGLITRONIC(鸿利光电)"))
      (libsource (lib "") (part "HL-A-5730D34WY-S1-08-CZ(LY)"))
    )
    (comp (ref "LED156")
      (value "HL-A-5730D34WY-S1-08-CZ(LY)")
      (fields (field (name "Manufacturer") "HONGLITRONIC(鸿利光电)"))
      (libsource (lib "") (part "HL-A-5730D34WY-S1-08-CZ(LY)"))
    )
    (comp (ref "LED157")
      (value "HL-A-5730D34WY-S1-08-CZ(LY)")
      (fields (field (name "Manufacturer") "HONGLITRONIC(鸿利光电)"))
      (libsource (lib "") (part "HL-A-5730D34WY-S1-08-CZ(LY)"))
    )
    (comp (ref "LED158")
      (value "HL-A-5730D34WY-S1-08-CZ(LY)")
      (fields (field (name "Manufacturer") "HONGLITRONIC(鸿利光电)"))
      (libsource (lib "") (part "HL-A-5730D34WY-S1-08-CZ(LY)"))
    )
    (comp (ref "LED159")
      (value "HL-A-5730D34WY-S1-08-CZ(LY)")
      (fields (field (name "Manufacturer") "HONGLITRONIC(鸿利光电)"))
      (libsource (lib "") (part "HL-A-5730D34WY-S1-08-CZ(LY)"))
    )
    (comp (ref "LED160")
      (value "HL-A-5730D34WY-S1-08-CZ(LY)")
      (fields (field (name "Manufacturer") "HONGLITRONIC(鸿利光电)"))
      (libsource (lib "") (part "HL-A-5730D34WY-S1-08-CZ(LY)"))
    )
    (comp (ref "LED161")
      (value "HL-A-5730D34WY-S1-08-CZ(LY)")
      (fields (field (name "Manufacturer") "HONGLITRONIC(鸿利光电)"))
      (libsource (lib "") (part "HL-A-5730D34WY-S1-08-CZ(LY)"))
    )
    (comp (ref "LED162")
      (value "HL-A-5730D34WY-S1-08-CZ(LY)")
      (fields (field (name "Manufacturer") "HONGLITRONIC(鸿利光电)"))
      (libsource (lib "") (part "HL-A-5730D34WY-S1-08-CZ(LY)"))
    )
    (comp (ref "LED163")
      (value "HL-A-5730D34WY-S1-08-CZ(LY)")
      (fields (field (name "Manufacturer") "HONGLITRONIC(鸿利光电)"))
      (libsource (lib "") (part "HL-A-5730D34WY-S1-08-CZ(LY)"))
    )
    (comp (ref "LED164")
      (value "HL-A-5730D34WY-S1-08-CZ(LY)")
      (fields (field (name "Manufacturer") "HONGLITRONIC(鸿利光电)"))
      (libsource (lib "") (part "HL-A-5730D34WY-S1-08-CZ(LY)"))
    )
    (comp (ref "LED165")
      (value "HL-A-5730D34WY-S1-08-CZ(LY)")
      (fields (field (name "Manufacturer") "HONGLITRONIC(鸿利光电)"))
      (libsource (lib "") (part "HL-A-5730D34WY-S1-08-CZ(LY)"))
    )
    (comp (ref "LED166")
      (value "HL-A-5730D34WY-S1-08-CZ(LY)")
      (fields (field (name "Manufacturer") "HONGLITRONIC(鸿利光电)"))
      (libsource (lib "") (part "HL-A-5730D34WY-S1-08-CZ(LY)"))
    )
    (comp (ref "LED167")
      (value "HL-A-5730D34WY-S1-08-CZ(LY)")
      (fields (field (name "Manufacturer") "HONGLITRONIC(鸿利光电)"))
      (libsource (lib "") (part "HL-A-5730D34WY-S1-08-CZ(LY)"))
    )
    (comp (ref "LED168")
      (value "HL-A-5730D34WY-S1-08-CZ(LY)")
      (fields (field (name "Manufacturer") "HONGLITRONIC(鸿利光电)"))
      (libsource (lib "") (part "HL-A-5730D34WY-S1-08-CZ(LY)"))
    )
    (comp (ref "LED169")
      (value "HL-A-5730D34WY-S1-08-CZ(LY)")
      (fields (field (name "Manufacturer") "HONGLITRONIC(鸿利光电)"))
      (libsource (lib "") (part "HL-A-5730D34WY-S1-08-CZ(LY)"))
    )
    (comp (ref "LED170")
      (value "HL-A-5730D34WY-S1-08-CZ(LY)")
      (fields (field (name "Manufacturer") "HONGLITRONIC(鸿利光电)"))
      (libsource (lib "") (part "HL-A-5730D34WY-S1-08-CZ(LY)"))
    )
    (comp (ref "LED171")
      (value "HL-A-5730D34WY-S1-08-CZ(LY)")
      (fields (field (name "Manufacturer") "HONGLITRONIC(鸿利光电)"))
      (libsource (lib "") (part "HL-A-5730D34WY-S1-08-CZ(LY)"))
    )
    (comp (ref "LED172")
      (value "HL-A-5730D34WY-S1-08-CZ(LY)")
      (fields (field (name "Manufacturer") "HONGLITRONIC(鸿利光电)"))
      (libsource (lib "") (part "HL-A-5730D34WY-S1-08-CZ(LY)"))
    )
    (comp (ref "LED173")
      (value "HL-A-5730D34WY-S1-08-CZ(LY)")
      (fields (field (name "Manufacturer") "HONGLITRONIC(鸿利光电)"))
      (libsource (lib "") (part "HL-A-5730D34WY-S1-08-CZ(LY)"))
    )
    (comp (ref "LED174")
      (value "HL-A-5730D34WY-S1-08-CZ(LY)")
      (fields (field (name "Manufacturer") "HONGLITRONIC(鸿利光电)"))
      (libsource (lib "") (part "HL-A-5730D34WY-S1-08-CZ(LY)"))
    )
    (comp (ref "LED175")
      (value "HL-A-5730D34WY-S1-08-CZ(LY)")
      (fields (field (name "Manufacturer") "HONGLITRONIC(鸿利光电)"))
      (libsource (lib "") (part "HL-A-5730D34WY-S1-08-CZ(LY)"))
    )
    (comp (ref "LED176")
      (value "HL-A-5730D34WY-S1-08-CZ(LY)")
      (fields (field (name "Manufacturer") "HONGLITRONIC(鸿利光电)"))
      (libsource (lib "") (part "HL-A-5730D34WY-S1-08-CZ(LY)"))
    )
    (comp (ref "LED177")
      (value "HL-A-5730D34WY-S1-08-CZ(LY)")
      (fields (field (name "Manufacturer") "HONGLITRONIC(鸿利光电)"))
      (libsource (lib "") (part "HL-A-5730D34WY-S1-08-CZ(LY)"))
    )
    (comp (ref "LED178")
      (value "HL-A-5730D34WY-S1-08-CZ(LY)")
      (fields (field (name "Manufacturer") "HONGLITRONIC(鸿利光电)"))
      (libsource (lib "") (part "HL-A-5730D34WY-S1-08-CZ(LY)"))
    )
    (comp (ref "LED179")
      (value "HL-A-5730D34WY-S1-08-CZ(LY)")
      (fields (field (name "Manufacturer") "HONGLITRONIC(鸿利光电)"))
      (libsource (lib "") (part "HL-A-5730D34WY-S1-08-CZ(LY)"))
    )
    (comp (ref "LED180")
      (value "HL-A-5730D34WY-S1-08-CZ(LY)")
      (fields (field (name "Manufacturer") "HONGLITRONIC(鸿利光电)"))
      (libsource (lib "") (part "HL-A-5730D34WY-S1-08-CZ(LY)"))
    )
    (comp (ref "LED181")
      (value "HL-A-5730D34WY-S1-08-CZ(LY)")
      (fields (field (name "Manufacturer") "HONGLITRONIC(鸿利光电)"))
      (libsource (lib "") (part "HL-A-5730D34WY-S1-08-CZ(LY)"))
    )
    (comp (ref "LED182")
      (value "HL-A-5730D34WY-S1-08-CZ(LY)")
      (fields (field (name "Manufacturer") "HONGLITRONIC(鸿利光电)"))
      (libsource (lib "") (part "HL-A-5730D34WY-S1-08-CZ(LY)"))
    )
    (comp (ref "LED183")
      (value "HL-A-5730D34WY-S1-08-CZ(LY)")
      (fields (field (name "Manufacturer") "HONGLITRONIC(鸿利光电)"))
      (libsource (lib "") (part "HL-A-5730D34WY-S1-08-CZ(LY)"))
    )
    (comp (ref "LED184")
      (value "HL-A-5730D34WY-S1-08-CZ(LY)")
      (fields (field (name "Manufacturer") "HONGLITRONIC(鸿利光电)"))
      (libsource (lib "") (part "HL-A-5730D34WY-S1-08-CZ(LY)"))
    )
    (comp (ref "LED185")
      (value "HL-A-5730D34WY-S1-08-CZ(LY)")
      (fields (field (name "Manufacturer") "HONGLITRONIC(鸿利光电)"))
      (libsource (lib "") (part "HL-A-5730D34WY-S1-08-CZ(LY)"))
    )
    (comp (ref "LED186")
      (value "HL-A-5730D34WY-S1-08-CZ(LY)")
      (fields (field (name "Manufacturer") "HONGLITRONIC(鸿利光电)"))
      (libsource (lib "") (part "HL-A-5730D34WY-S1-08-CZ(LY)"))
    )
    (comp (ref "LED187")
      (value "HL-A-5730D34WY-S1-08-CZ(LY)")
      (fields (field (name "Manufacturer") "HONGLITRONIC(鸿利光电)"))
      (libsource (lib "") (part "HL-A-5730D34WY-S1-08-CZ(LY)"))
    )
    (comp (ref "LED188")
      (value "HL-A-5730D34WY-S1-08-CZ(LY)")
      (fields (field (name "Manufacturer") "HONGLITRONIC(鸿利光电)"))
      (libsource (lib "") (part "HL-A-5730D34WY-S1-08-CZ(LY)"))
    )
    (comp (ref "LED189")
      (value "HL-A-5730D34WY-S1-08-CZ(LY)")
      (fields (field (name "Manufacturer") "HONGLITRONIC(鸿利光电)"))
      (libsource (lib "") (part "HL-A-5730D34WY-S1-08-CZ(LY)"))
    )
    (comp (ref "LED190")
      (value "HL-A-5730D34WY-S1-08-CZ(LY)")
      (fields (field (name "Manufacturer") "HONGLITRONIC(鸿利光电)"))
      (libsource (lib "") (part "HL-A-5730D34WY-S1-08-CZ(LY)"))
    )
    (comp (ref "LED191")
      (value "HL-A-5730D34WY-S1-08-CZ(LY)")
      (fields (field (name "Manufacturer") "HONGLITRONIC(鸿利光电)"))
      (libsource (lib "") (part "HL-A-5730D34WY-S1-08-CZ(LY)"))
    )
    (comp (ref "LED192")
      (value "HL-A-5730D34WY-S1-08-CZ(LY)")
      (fields (field (name "Manufacturer") "HONGLITRONIC(鸿利光电)"))
      (libsource (lib "") (part "HL-A-5730D34WY-S1-08-CZ(LY)"))
    )
    (comp (ref "LED193")
      (value "HL-A-5730D34WY-S1-08-CZ(LY)")
      (fields (field (name "Manufacturer") "HONGLITRONIC(鸿利光电)"))
      (libsource (lib "") (part "HL-A-5730D34WY-S1-08-CZ(LY)"))
    )
    (comp (ref "LED194")
      (value "HL-A-5730D34WY-S1-08-CZ(LY)")
      (fields (field (name "Manufacturer") "HONGLITRONIC(鸿利光电)"))
      (libsource (lib "") (part "HL-A-5730D34WY-S1-08-CZ(LY)"))
    )
    (comp (ref "LED195")
      (value "HL-A-5730D34WY-S1-08-CZ(LY)")
      (fields (field (name "Manufacturer") "HONGLITRONIC(鸿利光电)"))
      (libsource (lib "") (part "HL-A-5730D34WY-S1-08-CZ(LY)"))
    )
    (comp (ref "LED196")
      (value "HL-A-5730D34WY-S1-08-CZ(LY)")
      (fields (field (name "Manufacturer") "HONGLITRONIC(鸿利光电)"))
      (libsource (lib "") (part "HL-A-5730D34WY-S1-08-CZ(LY)"))
    )
    (comp (ref "LED197")
      (value "HL-A-5730D34WY-S1-08-CZ(LY)")
      (fields (field (name "Manufacturer") "HONGLITRONIC(鸿利光电)"))
      (libsource (lib "") (part "HL-A-5730D34WY-S1-08-CZ(LY)"))
    )
    (comp (ref "LED198")
      (value "HL-A-5730D34WY-S1-08-CZ(LY)")
      (fields (field (name "Manufacturer") "HONGLITRONIC(鸿利光电)"))
      (libsource (lib "") (part "HL-A-5730D34WY-S1-08-CZ(LY)"))
    )
    (comp (ref "LED199")
      (value "HL-A-5730D34WY-S1-08-CZ(LY)")
      (fields (field (name "Manufacturer") "HONGLITRONIC(鸿利光电)"))
      (libsource (lib "") (part "HL-A-5730D34WY-S1-08-CZ(LY)"))
    )
    (comp (ref "LED200")
      (value "HL-A-5730D34WY-S1-08-CZ(LY)")
      (fields (field (name "Manufacturer") "HONGLITRONIC(鸿利光电)"))
      (libsource (lib "") (part "HL-A-5730D34WY-S1-08-CZ(LY)"))
    )
    (comp (ref "LED201")
      (value "HL-A-5730D34WY-S1-08-CZ(LY)")
      (fields (field (name "Manufacturer") "HONGLITRONIC(鸿利光电)"))
      (libsource (lib "") (part "HL-A-5730D34WY-S1-08-CZ(LY)"))
    )
    (comp (ref "LED202")
      (value "HL-A-5730D34WY-S1-08-CZ(LY)")
      (fields (field (name "Manufacturer") "HONGLITRONIC(鸿利光电)"))
      (libsource (lib "") (part "HL-A-5730D34WY-S1-08-CZ(LY)"))
    )
    (comp (ref "LED203")
      (value "HL-A-5730D34WY-S1-08-CZ(LY)")
      (fields (field (name "Manufacturer") "HONGLITRONIC(鸿利光电)"))
      (libsource (lib "") (part "HL-A-5730D34WY-S1-08-CZ(LY)"))
    )
    (comp (ref "LED204")
      (value "HL-A-5730D34WY-S1-08-CZ(LY)")
      (fields (field (name "Manufacturer") "HONGLITRONIC(鸿利光电)"))
      (libsource (lib "") (part "HL-A-5730D34WY-S1-08-CZ(LY)"))
    )
    (comp (ref "LED205")
      (value "HL-A-5730D34WY-S1-08-CZ(LY)")
      (fields (field (name "Manufacturer") "HONGLITRONIC(鸿利光电)"))
      (libsource (lib "") (part "HL-A-5730D34WY-S1-08-CZ(LY)"))
    )
    (comp (ref "LED206")
      (value "HL-A-5730D34WY-S1-08-CZ(LY)")
      (fields (field (name "Manufacturer") "HONGLITRONIC(鸿利光电)"))
      (libsource (lib "") (part "HL-A-5730D34WY-S1-08-CZ(LY)"))
    )
    (comp (ref "LED207")
      (value "HL-A-5730D34WY-S1-08-CZ(LY)")
      (fields (field (name "Manufacturer") "HONGLITRONIC(鸿利光电)"))
      (libsource (lib "") (part "HL-A-5730D34WY-S1-08-CZ(LY)"))
    )
    (comp (ref "LED208")
      (value "HL-A-5730D34WY-S1-08-CZ(LY)")
      (fields (field (name "Manufacturer") "HONGLITRONIC(鸿利光电)"))
      (libsource (lib "") (part "HL-A-5730D34WY-S1-08-CZ(LY)"))
    )
    (comp (ref "LED209")
      (value "HL-A-5730D34WY-S1-08-CZ(LY)")
      (fields (field (name "Manufacturer") "HONGLITRONIC(鸿利光电)"))
      (libsource (lib "") (part "HL-A-5730D34WY-S1-08-CZ(LY)"))
    )
    (comp (ref "LED210")
      (value "HL-A-5730D34WY-S1-08-CZ(LY)")
      (fields (field (name "Manufacturer") "HONGLITRONIC(鸿利光电)"))
      (libsource (lib "") (part "HL-A-5730D34WY-S1-08-CZ(LY)"))
    )
    (comp (ref "LED211")
      (value "HL-A-5730D34WY-S1-08-CZ(LY)")
      (fields (field (name "Manufacturer") "HONGLITRONIC(鸿利光电)"))
      (libsource (lib "") (part "HL-A-5730D34WY-S1-08-CZ(LY)"))
    )
    (comp (ref "LED212")
      (value "HL-A-5730D34WY-S1-08-CZ(LY)")
      (fields (field (name "Manufacturer") "HONGLITRONIC(鸿利光电)"))
      (libsource (lib "") (part "HL-A-5730D34WY-S1-08-CZ(LY)"))
    )
    (comp (ref "LED213")
      (value "HL-A-5730D34WY-S1-08-CZ(LY)")
      (fields (field (name "Manufacturer") "HONGLITRONIC(鸿利光电)"))
      (libsource (lib "") (part "HL-A-5730D34WY-S1-08-CZ(LY)"))
    )
    (comp (ref "LED214")
      (value "HL-A-5730D34WY-S1-08-CZ(LY)")
      (fields (field (name "Manufacturer") "HONGLITRONIC(鸿利光电)"))
      (libsource (lib "") (part "HL-A-5730D34WY-S1-08-CZ(LY)"))
    )
    (comp (ref "LED215")
      (value "HL-A-5730D34WY-S1-08-CZ(LY)")
      (fields (field (name "Manufacturer") "HONGLITRONIC(鸿利光电)"))
      (libsource (lib "") (part "HL-A-5730D34WY-S1-08-CZ(LY)"))
    )
    (comp (ref "LED216")
      (value "HL-A-5730D34WY-S1-08-CZ(LY)")
      (fields (field (name "Manufacturer") "HONGLITRONIC(鸿利光电)"))
      (libsource (lib "") (part "HL-A-5730D34WY-S1-08-CZ(LY)"))
    )
    (comp (ref "LED217")
      (value "HL-A-5730D34WY-S1-08-CZ(LY)")
      (fields (field (name "Manufacturer") "HONGLITRONIC(鸿利光电)"))
      (libsource (lib "") (part "HL-A-5730D34WY-S1-08-CZ(LY)"))
    )
    (comp (ref "LED218")
      (value "HL-A-5730D34WY-S1-08-CZ(LY)")
      (fields (field (name "Manufacturer") "HONGLITRONIC(鸿利光电)"))
      (libsource (lib "") (part "HL-A-5730D34WY-S1-08-CZ(LY)"))
    )
    (comp (ref "LED219")
      (value "HL-A-5730D34WY-S1-08-CZ(LY)")
      (fields (field (name "Manufacturer") "HONGLITRONIC(鸿利光电)"))
      (libsource (lib "") (part "HL-A-5730D34WY-S1-08-CZ(LY)"))
    )
    (comp (ref "LED220")
      (value "HL-A-5730D34WY-S1-08-CZ(LY)")
      (fields (field (name "Manufacturer") "HONGLITRONIC(鸿利光电)"))
      (libsource (lib "") (part "HL-A-5730D34WY-S1-08-CZ(LY)"))
    )
    (comp (ref "LED221")
      (value "HL-A-5730D34WY-S1-08-CZ(LY)")
      (fields (field (name "Manufacturer") "HONGLITRONIC(鸿利光电)"))
      (libsource (lib "") (part "HL-A-5730D34WY-S1-08-CZ(LY)"))
    )
    (comp (ref "LED222")
      (value "HL-A-5730D34WY-S1-08-CZ(LY)")
      (fields (field (name "Manufacturer") "HONGLITRONIC(鸿利光电)"))
      (libsource (lib "") (part "HL-A-5730D34WY-S1-08-CZ(LY)"))
    )
    (comp (ref "LED223")
      (value "HL-A-5730D34WY-S1-08-CZ(LY)")
      (fields (field (name "Manufacturer") "HONGLITRONIC(鸿利光电)"))
      (libsource (lib "") (part "HL-A-5730D34WY-S1-08-CZ(LY)"))
    )
    (comp (ref "LED224")
      (value "HL-A-5730D34WY-S1-08-CZ(LY)")
      (fields (field (name "Manufacturer") "HONGLITRONIC(鸿利光电)"))
      (libsource (lib "") (part "HL-A-5730D34WY-S1-08-CZ(LY)"))
    )
    (comp (ref "LED225")
      (value "HL-A-5730D34WY-S1-08-CZ(LY)")
      (fields (field (name "Manufacturer") "HONGLITRONIC(鸿利光电)"))
      (libsource (lib "") (part "HL-A-5730D34WY-S1-08-CZ(LY)"))
    )
    (comp (ref "LED226")
      (value "HL-A-5730D34WY-S1-08-CZ(LY)")
      (fields (field (name "Manufacturer") "HONGLITRONIC(鸿利光电)"))
      (libsource (lib "") (part "HL-A-5730D34WY-S1-08-CZ(LY)"))
    )
    (comp (ref "LED227")
      (value "HL-A-5730D34WY-S1-08-CZ(LY)")
      (fields (field (name "Manufacturer") "HONGLITRONIC(鸿利光电)"))
      (libsource (lib "") (part "HL-A-5730D34WY-S1-08-CZ(LY)"))
    )
    (comp (ref "LED228")
      (value "HL-A-5730D34WY-S1-08-CZ(LY)")
      (fields (field (name "Manufacturer") "HONGLITRONIC(鸿利光电)"))
      (libsource (lib "") (part "HL-A-5730D34WY-S1-08-CZ(LY)"))
    )
    (comp (ref "LED229")
      (value "HL-A-5730D34WY-S1-08-CZ(LY)")
      (fields (field (name "Manufacturer") "HONGLITRONIC(鸿利光电)"))
      (libsource (lib "") (part "HL-A-5730D34WY-S1-08-CZ(LY)"))
    )
    (comp (ref "LED230")
      (value "HL-A-5730D34WY-S1-08-CZ(LY)")
      (fields (field (name "Manufacturer") "HONGLITRONIC(鸿利光电)"))
      (libsource (lib "") (part "HL-A-5730D34WY-S1-08-CZ(LY)"))
    )
    (comp (ref "LED231")
      (value "HL-A-5730D34WY-S1-08-CZ(LY)")
      (fields (field (name "Manufacturer") "HONGLITRONIC(鸿利光电)"))
      (libsource (lib "") (part "HL-A-5730D34WY-S1-08-CZ(LY)"))
    )
    (comp (ref "LED232")
      (value "HL-A-5730D34WY-S1-08-CZ(LY)")
      (fields (field (name "Manufacturer") "HONGLITRONIC(鸿利光电)"))
      (libsource (lib "") (part "HL-A-5730D34WY-S1-08-CZ(LY)"))
    )
    (comp (ref "LED233")
      (value "HL-A-5730D34WY-S1-08-CZ(LY)")
      (fields (field (name "Manufacturer") "HONGLITRONIC(鸿利光电)"))
      (libsource (lib "") (part "HL-A-5730D34WY-S1-08-CZ(LY)"))
    )
    (comp (ref "LED234")
      (value "HL-A-5730D34WY-S1-08-CZ(LY)")
      (fields (field (name "Manufacturer") "HONGLITRONIC(鸿利光电)"))
      (libsource (lib "") (part "HL-A-5730D34WY-S1-08-CZ(LY)"))
    )
    (comp (ref "LED235")
      (value "HL-A-5730D34WY-S1-08-CZ(LY)")
      (fields (field (name "Manufacturer") "HONGLITRONIC(鸿利光电)"))
      (libsource (lib "") (part "HL-A-5730D34WY-S1-08-CZ(LY)"))
    )
    (comp (ref "LED236")
      (value "HL-A-5730D34WY-S1-08-CZ(LY)")
      (fields (field (name "Manufacturer") "HONGLITRONIC(鸿利光电)"))
      (libsource (lib "") (part "HL-A-5730D34WY-S1-08-CZ(LY)"))
    )
    (comp (ref "LED237")
      (value "HL-A-5730D34WY-S1-08-CZ(LY)")
      (fields (field (name "Manufacturer") "HONGLITRONIC(鸿利光电)"))
      (libsource (lib "") (part "HL-A-5730D34WY-S1-08-CZ(LY)"))
    )
    (comp (ref "LED238")
      (value "HL-A-5730D34WY-S1-08-CZ(LY)")
      (fields (field (name "Manufacturer") "HONGLITRONIC(鸿利光电)"))
      (libsource (lib "") (part "HL-A-5730D34WY-S1-08-CZ(LY)"))
    )
    (comp (ref "LED239")
      (value "HL-A-5730D34WY-S1-08-CZ(LY)")
      (fields (field (name "Manufacturer") "HONGLITRONIC(鸿利光电)"))
      (libsource (lib "") (part "HL-A-5730D34WY-S1-08-CZ(LY)"))
    )
    (comp (ref "LED240")
      (value "HL-A-5730D34WY-S1-08-CZ(LY)")
      (fields (field (name "Manufacturer") "HONGLITRONIC(鸿利光电)"))
      (libsource (lib "") (part "HL-A-5730D34WY-S1-08-CZ(LY)"))
    )
    (comp (ref "LED241")
      (value "HL-A-5730D34WY-S1-08-CZ(LY)")
      (fields (field (name "Manufacturer") "HONGLITRONIC(鸿利光电)"))
      (libsource (lib "") (part "HL-A-5730D34WY-S1-08-CZ(LY)"))
    )
    (comp (ref "LED242")
      (value "HL-A-5730D34WY-S1-08-CZ(LY)")
      (fields (field (name "Manufacturer") "HONGLITRONIC(鸿利光电)"))
      (libsource (lib "") (part "HL-A-5730D34WY-S1-08-CZ(LY)"))
    )
    (comp (ref "LED243")
      (value "HL-A-5730D34WY-S1-08-CZ(LY)")
      (fields (field (name "Manufacturer") "HONGLITRONIC(鸿利光电)"))
      (libsource (lib "") (part "HL-A-5730D34WY-S1-08-CZ(LY)"))
    )
    (comp (ref "LED244")
      (value "HL-A-5730D34WY-S1-08-CZ(LY)")
      (fields (field (name "Manufacturer") "HONGLITRONIC(鸿利光电)"))
      (libsource (lib "") (part "HL-A-5730D34WY-S1-08-CZ(LY)"))
    )
    (comp (ref "LED245")
      (value "HL-A-5730D34WY-S1-08-CZ(LY)")
      (fields (field (name "Manufacturer") "HONGLITRONIC(鸿利光电)"))
      (libsource (lib "") (part "HL-A-5730D34WY-S1-08-CZ(LY)"))
    )
    (comp (ref "LED246")
      (value "HL-A-5730D34WY-S1-08-CZ(LY)")
      (fields (field (name "Manufacturer") "HONGLITRONIC(鸿利光电)"))
      (libsource (lib "") (part "HL-A-5730D34WY-S1-08-CZ(LY)"))
    )
    (comp (ref "LED247")
      (value "HL-A-5730D34WY-S1-08-CZ(LY)")
      (fields (field (name "Manufacturer") "HONGLITRONIC(鸿利光电)"))
      (libsource (lib "") (part "HL-A-5730D34WY-S1-08-CZ(LY)"))
    )
    (comp (ref "LED248")
      (value "HL-A-5730D34WY-S1-08-CZ(LY)")
      (fields (field (name "Manufacturer") "HONGLITRONIC(鸿利光电)"))
      (libsource (lib "") (part "HL-A-5730D34WY-S1-08-CZ(LY)"))
    )
    (comp (ref "LED249")
      (value "HL-A-5730D34WY-S1-08-CZ(LY)")
      (fields (field (name "Manufacturer") "HONGLITRONIC(鸿利光电)"))
      (libsource (lib "") (part "HL-A-5730D34WY-S1-08-CZ(LY)"))
    )
    (comp (ref "LED250")
      (value "HL-A-5730D34WY-S1-08-CZ(LY)")
      (fields (field (name "Manufacturer") "HONGLITRONIC(鸿利光电)"))
      (libsource (lib "") (part "HL-A-5730D34WY-S1-08-CZ(LY)"))
    )
    (comp (ref "LED251")
      (value "HL-A-5730D34WY-S1-08-CZ(LY)")
      (fields (field (name "Manufacturer") "HONGLITRONIC(鸿利光电)"))
      (libsource (lib "") (part "HL-A-5730D34WY-S1-08-CZ(LY)"))
    )
    (comp (ref "LED252")
      (value "HL-A-5730D34WY-S1-08-CZ(LY)")
      (fields (field (name "Manufacturer") "HONGLITRONIC(鸿利光电)"))
      (libsource (lib "") (part "HL-A-5730D34WY-S1-08-CZ(LY)"))
    )
    (comp (ref "LED253")
      (value "HL-A-5730D34WY-S1-08-CZ(LY)")
      (fields (field (name "Manufacturer") "HONGLITRONIC(鸿利光电)"))
      (libsource (lib "") (part "HL-A-5730D34WY-S1-08-CZ(LY)"))
    )
    (comp (ref "LED254")
      (value "HL-A-5730D34WY-S1-08-CZ(LY)")
      (fields (field (name "Manufacturer") "HONGLITRONIC(鸿利光电)"))
      (libsource (lib "") (part "HL-A-5730D34WY-S1-08-CZ(LY)"))
    )
    (comp (ref "LED255")
      (value "HL-A-5730D34WY-S1-08-CZ(LY)")
      (fields (field (name "Manufacturer") "HONGLITRONIC(鸿利光电)"))
      (libsource (lib "") (part "HL-A-5730D34WY-S1-08-CZ(LY)"))
    )
    (comp (ref "LED256")
      (value "HL-A-5730D34WY-S1-08-CZ(LY)")
      (fields (field (name "Manufacturer") "HONGLITRONIC(鸿利光电)"))
      (libsource (lib "") (part "HL-A-5730D34WY-S1-08-CZ(LY)"))
    )
    (comp (ref "R1") (value "1M") (libsource (lib "") (part "R_0603_EU_1")))
    (comp (ref "R2") (value "2.2k") (libsource (lib "") (part "R_0603_EU")))
    (comp (ref "R3") (value "10k") (libsource (lib "") (part "R_0603_EU_1")))
    (comp (ref "U1")
      (value "74HC238D")
      (fields (field (name "Manufacturer Part") "74HC238D,653") (field (name "Manufacturer") "Nexperia(安世)"))
      (libsource (lib "") (part "74HC238D"))
    )
    (comp (ref "U2")
      (value "CD74HC4060M96")
      (fields (field (name "Manufacturer") "TI(德州仪器)"))
      (libsource (lib "") (part "CD74HC4060M96"))
    )
    (comp (ref "U3")
      (value "74HC238D")
      (fields (field (name "Manufacturer Part") "74HC238D,653") (field (name "Manufacturer") "Nexperia(安世)"))
      (libsource (lib "") (part "74HC238D"))
    )
    (comp (ref "X1")
      (value "32.768kHz")
      (fields
        (field (name "Manufacturer Part") "SCFYS32X76800YERN")
        (field (name "Manufacturer") "SOSET(索斯特)")
      )
      (libsource (lib "") (part "SCFYS32X76800YERN"))
    )
  )
  (nets
    (net (code "1") (name "+3.3V") (class "Default")
      (node (ref "C1") (pin "2") (pinfunction "2_2") (pintype "unspecified"))
      (node (ref "C2") (pin "2") (pinfunction "2_2") (pintype "unspecified"))
      (node (ref "U1") (pin "16") (pinfunction "VCC_16") (pintype "unspecified"))
      (node (ref "U2") (pin "16") (pinfunction "VCC_16") (pintype "unspecified"))
      (node (ref "U3") (pin "16") (pinfunction "VCC_16") (pintype "unspecified"))
    )
    (net (code "2") (name "1") (class "Default")
      (node (ref "LED105") (pin "2") (pinfunction "A_2") (pintype "unspecified"))
      (node (ref "LED121") (pin "2") (pinfunction "A_2") (pintype "unspecified"))
      (node (ref "LED136") (pin "2") (pinfunction "A_2") (pintype "unspecified"))
      (node (ref "LED152") (pin "2") (pinfunction "A_2") (pintype "unspecified"))
      (node (ref "LED168") (pin "2") (pinfunction "A_2") (pintype "unspecified"))
      (node (ref "LED184") (pin "2") (pinfunction "A_2") (pintype "unspecified"))
      (node (ref "LED200") (pin "2") (pinfunction "A_2") (pintype "unspecified"))
      (node (ref "LED216") (pin "2") (pinfunction "A_2") (pintype "unspecified"))
      (node (ref "LED232") (pin "2") (pinfunction "A_2") (pintype "unspecified"))
      (node (ref "LED24") (pin "2") (pinfunction "A_2") (pintype "unspecified"))
      (node (ref "LED248") (pin "2") (pinfunction "A_2") (pintype "unspecified"))
      (node (ref "LED41") (pin "2") (pinfunction "A_2") (pintype "unspecified"))
      (node (ref "LED57") (pin "2") (pinfunction "A_2") (pintype "unspecified"))
      (node (ref "LED73") (pin "2") (pinfunction "A_2") (pintype "unspecified"))
      (node (ref "LED89") (pin "2") (pinfunction "A_2") (pintype "unspecified"))
      (node (ref "LED9") (pin "2") (pinfunction "A_2") (pintype "unspecified"))
    )
    (net (code "3") (name "2") (class "Default")
      (node (ref "LED10") (pin "2") (pinfunction "A_2") (pintype "unspecified"))
      (node (ref "LED106") (pin "2") (pinfunction "A_2") (pintype "unspecified"))
      (node (ref "LED122") (pin "2") (pinfunction "A_2") (pintype "unspecified"))
      (node (ref "LED135") (pin "2") (pinfunction "A_2") (pintype "unspecified"))
      (node (ref "LED151") (pin "2") (pinfunction "A_2") (pintype "unspecified"))
      (node (ref "LED167") (pin "2") (pinfunction "A_2") (pintype "unspecified"))
      (node (ref "LED183") (pin "2") (pinfunction "A_2") (pintype "unspecified"))
      (node (ref "LED199") (pin "2") (pinfunction "A_2") (pintype "unspecified"))
      (node (ref "LED215") (pin "2") (pinfunction "A_2") (pintype "unspecified"))
      (node (ref "LED23") (pin "2") (pinfunction "A_2") (pintype "unspecified"))
      (node (ref "LED231") (pin "2") (pinfunction "A_2") (pintype "unspecified"))
      (node (ref "LED247") (pin "2") (pinfunction "A_2") (pintype "unspecified"))
      (node (ref "LED42") (pin "2") (pinfunction "A_2") (pintype "unspecified"))
      (node (ref "LED58") (pin "2") (pinfunction "A_2") (pintype "unspecified"))
      (node (ref "LED74") (pin "2") (pinfunction "A_2") (pintype "unspecified"))
      (node (ref "LED90") (pin "2") (pinfunction "A_2") (pintype "unspecified"))
    )
    (net (code "4") (name "3") (class "Default")
      (node (ref "LED107") (pin "2") (pinfunction "A_2") (pintype "unspecified"))
      (node (ref "LED11") (pin "2") (pinfunction "A_2") (pintype "unspecified"))
      (node (ref "LED123") (pin "2") (pinfunction "A_2") (pintype "unspecified"))
      (node (ref "LED134") (pin "2") (pinfunction "A_2") (pintype "unspecified"))
      (node (ref "LED150") (pin "2") (pinfunction "A_2") (pintype "unspecified"))
      (node (ref "LED166") (pin "2") (pinfunction "A_2") (pintype "unspecified"))
      (node (ref "LED182") (pin "2") (pinfunction "A_2") (pintype "unspecified"))
      (node (ref "LED198") (pin "2") (pinfunction "A_2") (pintype "unspecified"))
      (node (ref "LED214") (pin "2") (pinfunction "A_2") (pintype "unspecified"))
      (node (ref "LED22") (pin "2") (pinfunction "A_2") (pintype "unspecified"))
      (node (ref "LED230") (pin "2") (pinfunction "A_2") (pintype "unspecified"))
      (node (ref "LED246") (pin "2") (pinfunction "A_2") (pintype "unspecified"))
      (node (ref "LED43") (pin "2") (pinfunction "A_2") (pintype "unspecified"))
      (node (ref "LED59") (pin "2") (pinfunction "A_2") (pintype "unspecified"))
      (node (ref "LED75") (pin "2") (pinfunction "A_2") (pintype "unspecified"))
      (node (ref "LED91") (pin "2") (pinfunction "A_2") (pintype "unspecified"))
    )
    (net (code "5") (name "4") (class "Default")
      (node (ref "LED108") (pin "2") (pinfunction "A_2") (pintype "unspecified"))
      (node (ref "LED12") (pin "2") (pinfunction "A_2") (pintype "unspecified"))
      (node (ref "LED124") (pin "2") (pinfunction "A_2") (pintype "unspecified"))
      (node (ref "LED133") (pin "2") (pinfunction "A_2") (pintype "unspecified"))
      (node (ref "LED149") (pin "2") (pinfunction "A_2") (pintype "unspecified"))
      (node (ref "LED165") (pin "2") (pinfunction "A_2") (pintype "unspecified"))
      (node (ref "LED181") (pin "2") (pinfunction "A_2") (pintype "unspecified"))
      (node (ref "LED197") (pin "2") (pinfunction "A_2") (pintype "unspecified"))
      (node (ref "LED21") (pin "2") (pinfunction "A_2") (pintype "unspecified"))
      (node (ref "LED213") (pin "2") (pinfunction "A_2") (pintype "unspecified"))
      (node (ref "LED229") (pin "2") (pinfunction "A_2") (pintype "unspecified"))
      (node (ref "LED245") (pin "2") (pinfunction "A_2") (pintype "unspecified"))
      (node (ref "LED44") (pin "2") (pinfunction "A_2") (pintype "unspecified"))
      (node (ref "LED60") (pin "2") (pinfunction "A_2") (pintype "unspecified"))
      (node (ref "LED76") (pin "2") (pinfunction "A_2") (pintype "unspecified"))
      (node (ref "LED92") (pin "2") (pinfunction "A_2") (pintype "unspecified"))
    )
    (net (code "6") (name "5") (class "Default")
      (node (ref "LED109") (pin "2") (pinfunction "A_2") (pintype "unspecified"))
      (node (ref "LED125") (pin "2") (pinfunction "A_2") (pintype "unspecified"))
      (node (ref "LED13") (pin "2") (pinfunction "A_2") (pintype "unspecified"))
      (node (ref "LED132") (pin "2") (pinfunction "A_2") (pintype "unspecified"))
      (node (ref "LED148") (pin "2") (pinfunction "A_2") (pintype "unspecified"))
      (node (ref "LED164") (pin "2") (pinfunction "A_2") (pintype "unspecified"))
      (node (ref "LED180") (pin "2") (pinfunction "A_2") (pintype "unspecified"))
      (node (ref "LED196") (pin "2") (pinfunction "A_2") (pintype "unspecified"))
      (node (ref "LED20") (pin "2") (pinfunction "A_2") (pintype "unspecified"))
      (node (ref "LED212") (pin "2") (pinfunction "A_2") (pintype "unspecified"))
      (node (ref "LED228") (pin "2") (pinfunction "A_2") (pintype "unspecified"))
      (node (ref "LED244") (pin "2") (pinfunction "A_2") (pintype "unspecified"))
      (node (ref "LED45") (pin "2") (pinfunction "A_2") (pintype "unspecified"))
      (node (ref "LED61") (pin "2") (pinfunction "A_2") (pintype "unspecified"))
      (node (ref "LED77") (pin "2") (pinfunction "A_2") (pintype "unspecified"))
      (node (ref "LED93") (pin "2") (pinfunction "A_2") (pintype "unspecified"))
    )
    (net (code "7") (name "6") (class "Default")
      (node (ref "LED110") (pin "2") (pinfunction "A_2") (pintype "unspecified"))
      (node (ref "LED126") (pin "2") (pinfunction "A_2") (pintype "unspecified"))
      (node (ref "LED131") (pin "2") (pinfunction "A_2") (pintype "unspecified"))
      (node (ref "LED14") (pin "2") (pinfunction "A_2") (pintype "unspecified"))
      (node (ref "LED147") (pin "2") (pinfunction "A_2") (pintype "unspecified"))
      (node (ref "LED163") (pin "2") (pinfunction "A_2") (pintype "unspecified"))
      (node (ref "LED179") (pin "2") (pinfunction "A_2") (pintype "unspecified"))
      (node (ref "LED19") (pin "2") (pinfunction "A_2") (pintype "unspecified"))
      (node (ref "LED195") (pin "2") (pinfunction "A_2") (pintype "unspecified"))
      (node (ref "LED211") (pin "2") (pinfunction "A_2") (pintype "unspecified"))
      (node (ref "LED227") (pin "2") (pinfunction "A_2") (pintype "unspecified"))
      (node (ref "LED243") (pin "2") (pinfunction "A_2") (pintype "unspecified"))
      (node (ref "LED46") (pin "2") (pinfunction "A_2") (pintype "unspecified"))
      (node (ref "LED62") (pin "2") (pinfunction "A_2") (pintype "unspecified"))
      (node (ref "LED78") (pin "2") (pinfunction "A_2") (pintype "unspecified"))
      (node (ref "LED94") (pin "2") (pinfunction "A_2") (pintype "unspecified"))
    )
    (net (code "8") (name "7") (class "Default")
      (node (ref "LED111") (pin "2") (pinfunction "A_2") (pintype "unspecified"))
      (node (ref "LED127") (pin "2") (pinfunction "A_2") (pintype "unspecified"))
      (node (ref "LED130") (pin "2") (pinfunction "A_2") (pintype "unspecified"))
      (node (ref "LED146") (pin "2") (pinfunction "A_2") (pintype "unspecified"))
      (node (ref "LED15") (pin "2") (pinfunction "A_2") (pintype "unspecified"))
      (node (ref "LED162") (pin "2") (pinfunction "A_2") (pintype "unspecified"))
      (node (ref "LED178") (pin "2") (pinfunction "A_2") (pintype "unspecified"))
      (node (ref "LED18") (pin "2") (pinfunction "A_2") (pintype "unspecified"))
      (node (ref "LED194") (pin "2") (pinfunction "A_2") (pintype "unspecified"))
      (node (ref "LED210") (pin "2") (pinfunction "A_2") (pintype "unspecified"))
      (node (ref "LED226") (pin "2") (pinfunction "A_2") (pintype "unspecified"))
      (node (ref "LED242") (pin "2") (pinfunction "A_2") (pintype "unspecified"))
      (node (ref "LED47") (pin "2") (pinfunction "A_2") (pintype "unspecified"))
      (node (ref "LED63") (pin "2") (pinfunction "A_2") (pintype "unspecified"))
      (node (ref "LED79") (pin "2") (pinfunction "A_2") (pintype "unspecified"))
      (node (ref "LED95") (pin "2") (pinfunction "A_2") (pintype "unspecified"))
    )
    (net (code "9") (name "8") (class "Default")
      (node (ref "LED112") (pin "2") (pinfunction "A_2") (pintype "unspecified"))
      (node (ref "LED128") (pin "2") (pinfunction "A_2") (pintype "unspecified"))
      (node (ref "LED129") (pin "2") (pinfunction "A_2") (pintype "unspecified"))
      (node (ref "LED145") (pin "2") (pinfunction "A_2") (pintype "unspecified"))
      (node (ref "LED16") (pin "2") (pinfunction "A_2") (pintype "unspecified"))
      (node (ref "LED161") (pin "2") (pinfunction "A_2") (pintype "unspecified"))
      (node (ref "LED17") (pin "2") (pinfunction "A_2") (pintype "unspecified"))
      (node (ref "LED177") (pin "2") (pinfunction "A_2") (pintype "unspecified"))
      (node (ref "LED193") (pin "2") (pinfunction "A_2") (pintype "unspecified"))
      (node (ref "LED209") (pin "2") (pinfunction "A_2") (pintype "unspecified"))
      (node (ref "LED225") (pin "2") (pinfunction "A_2") (pintype "unspecified"))
      (node (ref "LED241") (pin "2") (pinfunction "A_2") (pintype "unspecified"))
      (node (ref "LED48") (pin "2") (pinfunction "A_2") (pintype "unspecified"))
      (node (ref "LED64") (pin "2") (pinfunction "A_2") (pintype "unspecified"))
      (node (ref "LED80") (pin "2") (pinfunction "A_2") (pintype "unspecified"))
      (node (ref "LED96") (pin "2") (pinfunction "A_2") (pintype "unspecified"))
    )
    (net (code "10") (name "9") (class "Default")
      (node (ref "LED104") (pin "2") (pinfunction "A_2") (pintype "unspecified"))
      (node (ref "LED120") (pin "2") (pinfunction "A_2") (pintype "unspecified"))
      (node (ref "LED137") (pin "2") (pinfunction "A_2") (pintype "unspecified"))
      (node (ref "LED153") (pin "2") (pinfunction "A_2") (pintype "unspecified"))
      (node (ref "LED169") (pin "2") (pinfunction "A_2") (pintype "unspecified"))
      (node (ref "LED185") (pin "2") (pinfunction "A_2") (pintype "unspecified"))
      (node (ref "LED201") (pin "2") (pinfunction "A_2") (pintype "unspecified"))
      (node (ref "LED217") (pin "2") (pinfunction "A_2") (pintype "unspecified"))
      (node (ref "LED233") (pin "2") (pinfunction "A_2") (pintype "unspecified"))
      (node (ref "LED249") (pin "2") (pinfunction "A_2") (pintype "unspecified"))
      (node (ref "LED25") (pin "2") (pinfunction "A_2") (pintype "unspecified"))
      (node (ref "LED40") (pin "2") (pinfunction "A_2") (pintype "unspecified"))
      (node (ref "LED56") (pin "2") (pinfunction "A_2") (pintype "unspecified"))
      (node (ref "LED72") (pin "2") (pinfunction "A_2") (pintype "unspecified"))
      (node (ref "LED8") (pin "2") (pinfunction "A_2") (pintype "unspecified"))
      (node (ref "LED88") (pin "2") (pinfunction "A_2") (pintype "unspecified"))
    )
    (net (code "11") (name "10") (class "Default")
      (node (ref "LED103") (pin "2") (pinfunction "A_2") (pintype "unspecified"))
      (node (ref "LED119") (pin "2") (pinfunction "A_2") (pintype "unspecified"))
      (node (ref "LED138") (pin "2") (pinfunction "A_2") (pintype "unspecified"))
      (node (ref "LED154") (pin "2") (pinfunction "A_2") (pintype "unspecified"))
      (node (ref "LED170") (pin "2") (pinfunction "A_2") (pintype "unspecified"))
      (node (ref "LED186") (pin "2") (pinfunction "A_2") (pintype "unspecified"))
      (node (ref "LED202") (pin "2") (pinfunction "A_2") (pintype "unspecified"))
      (node (ref "LED218") (pin "2") (pinfunction "A_2") (pintype "unspecified"))
      (node (ref "LED234") (pin "2") (pinfunction "A_2") (pintype "unspecified"))
      (node (ref "LED250") (pin "2") (pinfunction "A_2") (pintype "unspecified"))
      (node (ref "LED26") (pin "2") (pinfunction "A_2") (pintype "unspecified"))
      (node (ref "LED39") (pin "2") (pinfunction "A_2") (pintype "unspecified"))
      (node (ref "LED55") (pin "2") (pinfunction "A_2") (pintype "unspecified"))
      (node (ref "LED7") (pin "2") (pinfunction "A_2") (pintype "unspecified"))
      (node (ref "LED71") (pin "2") (pinfunction "A_2") (pintype "unspecified"))
      (node (ref "LED87") (pin "2") (pinfunction "A_2") (pintype "unspecified"))
    )
    (net (code "12") (name "11") (class "Default")
      (node (ref "LED102") (pin "2") (pinfunction "A_2") (pintype "unspecified"))
      (node (ref "LED118") (pin "2") (pinfunction "A_2") (pintype "unspecified"))
      (node (ref "LED139") (pin "2") (pinfunction "A_2") (pintype "unspecified"))
      (node (ref "LED155") (pin "2") (pinfunction "A_2") (pintype "unspecified"))
      (node (ref "LED171") (pin "2") (pinfunction "A_2") (pintype "unspecified"))
      (node (ref "LED187") (pin "2") (pinfunction "A_2") (pintype "unspecified"))
      (node (ref "LED203") (pin "2") (pinfunction "A_2") (pintype "unspecified"))
      (node (ref "LED219") (pin "2") (pinfunction "A_2") (pintype "unspecified"))
      (node (ref "LED235") (pin "2") (pinfunction "A_2") (pintype "unspecified"))
      (node (ref "LED251") (pin "2") (pinfunction "A_2") (pintype "unspecified"))
      (node (ref "LED27") (pin "2") (pinfunction "A_2") (pintype "unspecified"))
      (node (ref "LED38") (pin "2") (pinfunction "A_2") (pintype "unspecified"))
      (node (ref "LED54") (pin "2") (pinfunction "A_2") (pintype "unspecified"))
      (node (ref "LED6") (pin "2") (pinfunction "A_2") (pintype "unspecified"))
      (node (ref "LED70") (pin "2") (pinfunction "A_2") (pintype "unspecified"))
      (node (ref "LED86") (pin "2") (pinfunction "A_2") (pintype "unspecified"))
    )
    (net (code "13") (name "12") (class "Default")
      (node (ref "LED101") (pin "2") (pinfunction "A_2") (pintype "unspecified"))
      (node (ref "LED117") (pin "2") (pinfunction "A_2") (pintype "unspecified"))
      (node (ref "LED140") (pin "2") (pinfunction "A_2") (pintype "unspecified"))
      (node (ref "LED156") (pin "2") (pinfunction "A_2") (pintype "unspecified"))
      (node (ref "LED172") (pin "2") (pinfunction "A_2") (pintype "unspecified"))
      (node (ref "LED188") (pin "2") (pinfunction "A_2") (pintype "unspecified"))
      (node (ref "LED204") (pin "2") (pinfunction "A_2") (pintype "unspecified"))
      (node (ref "LED220") (pin "2") (pinfunction "A_2") (pintype "unspecified"))
      (node (ref "LED236") (pin "2") (pinfunction "A_2") (pintype "unspecified"))
      (node (ref "LED252") (pin "2") (pinfunction "A_2") (pintype "unspecified"))
      (node (ref "LED28") (pin "2") (pinfunction "A_2") (pintype "unspecified"))
      (node (ref "LED37") (pin "2") (pinfunction "A_2") (pintype "unspecified"))
      (node (ref "LED5") (pin "2") (pinfunction "A_2") (pintype "unspecified"))
      (node (ref "LED53") (pin "2") (pinfunction "A_2") (pintype "unspecified"))
      (node (ref "LED69") (pin "2") (pinfunction "A_2") (pintype "unspecified"))
      (node (ref "LED85") (pin "2") (pinfunction "A_2") (pintype "unspecified"))
    )
    (net (code "14") (name "13") (class "Default")
      (node (ref "LED100") (pin "2") (pinfunction "A_2") (pintype "unspecified"))
      (node (ref "LED116") (pin "2") (pinfunction "A_2") (pintype "unspecified"))
      (node (ref "LED141") (pin "2") (pinfunction "A_2") (pintype "unspecified"))
      (node (ref "LED157") (pin "2") (pinfunction "A_2") (pintype "unspecified"))
      (node (ref "LED173") (pin "2") (pinfunction "A_2") (pintype "unspecified"))
      (node (ref "LED189") (pin "2") (pinfunction "A_2") (pintype "unspecified"))
      (node (ref "LED205") (pin "2") (pinfunction "A_2") (pintype "unspecified"))
      (node (ref "LED221") (pin "2") (pinfunction "A_2") (pintype "unspecified"))
      (node (ref "LED237") (pin "2") (pinfunction "A_2") (pintype "unspecified"))
      (node (ref "LED253") (pin "2") (pinfunction "A_2") (pintype "unspecified"))
      (node (ref "LED29") (pin "2") (pinfunction "A_2") (pintype "unspecified"))
      (node (ref "LED36") (pin "2") (pinfunction "A_2") (pintype "unspecified"))
      (node (ref "LED4") (pin "2") (pinfunction "A_2") (pintype "unspecified"))
      (node (ref "LED52") (pin "2") (pinfunction "A_2") (pintype "unspecified"))
      (node (ref "LED68") (pin "2") (pinfunction "A_2") (pintype "unspecified"))
      (node (ref "LED84") (pin "2") (pinfunction "A_2") (pintype "unspecified"))
    )
    (net (code "15") (name "14") (class "Default")
      (node (ref "LED115") (pin "2") (pinfunction "A_2") (pintype "unspecified"))
      (node (ref "LED142") (pin "2") (pinfunction "A_2") (pintype "unspecified"))
      (node (ref "LED158") (pin "2") (pinfunction "A_2") (pintype "unspecified"))
      (node (ref "LED174") (pin "2") (pinfunction "A_2") (pintype "unspecified"))
      (node (ref "LED190") (pin "2") (pinfunction "A_2") (pintype "unspecified"))
      (node (ref "LED206") (pin "2") (pinfunction "A_2") (pintype "unspecified"))
      (node (ref "LED222") (pin "2") (pinfunction "A_2") (pintype "unspecified"))
      (node (ref "LED238") (pin "2") (pinfunction "A_2") (pintype "unspecified"))
      (node (ref "LED254") (pin "2") (pinfunction "A_2") (pintype "unspecified"))
      (node (ref "LED3") (pin "2") (pinfunction "A_2") (pintype "unspecified"))
      (node (ref "LED30") (pin "2") (pinfunction "A_2") (pintype "unspecified"))
      (node (ref "LED35") (pin "2") (pinfunction "A_2") (pintype "unspecified"))
      (node (ref "LED51") (pin "2") (pinfunction "A_2") (pintype "unspecified"))
      (node (ref "LED67") (pin "2") (pinfunction "A_2") (pintype "unspecified"))
      (node (ref "LED83") (pin "2") (pinfunction "A_2") (pintype "unspecified"))
      (node (ref "LED99") (pin "2") (pinfunction "A_2") (pintype "unspecified"))
    )
    (net (code "16") (name "15") (class "Default")
      (node (ref "LED114") (pin "2") (pinfunction "A_2") (pintype "unspecified"))
      (node (ref "LED143") (pin "2") (pinfunction "A_2") (pintype "unspecified"))
      (node (ref "LED159") (pin "2") (pinfunction "A_2") (pintype "unspecified"))
      (node (ref "LED175") (pin "2") (pinfunction "A_2") (pintype "unspecified"))
      (node (ref "LED191") (pin "2") (pinfunction "A_2") (pintype "unspecified"))
      (node (ref "LED2") (pin "2") (pinfunction "A_2") (pintype "unspecified"))
      (node (ref "LED207") (pin "2") (pinfunction "A_2") (pintype "unspecified"))
      (node (ref "LED223") (pin "2") (pinfunction "A_2") (pintype "unspecified"))
      (node (ref "LED239") (pin "2") (pinfunction "A_2") (pintype "unspecified"))
      (node (ref "LED255") (pin "2") (pinfunction "A_2") (pintype "unspecified"))
      (node (ref "LED31") (pin "2") (pinfunction "A_2") (pintype "unspecified"))
      (node (ref "LED34") (pin "2") (pinfunction "A_2") (pintype "unspecified"))
      (node (ref "LED50") (pin "2") (pinfunction "A_2") (pintype "unspecified"))
      (node (ref "LED66") (pin "2") (pinfunction "A_2") (pintype "unspecified"))
      (node (ref "LED82") (pin "2") (pinfunction "A_2") (pintype "unspecified"))
      (node (ref "LED98") (pin "2") (pinfunction "A_2") (pintype "unspecified"))
    )
    (net (code "17") (name "16") (class "Default")
      (node (ref "LED1") (pin "2") (pinfunction "A_2") (pintype "unspecified"))
      (node (ref "LED113") (pin "2") (pinfunction "A_2") (pintype "unspecified"))
      (node (ref "LED144") (pin "2") (pinfunction "A_2") (pintype "unspecified"))
      (node (ref "LED160") (pin "2") (pinfunction "A_2") (pintype "unspecified"))
      (node (ref "LED176") (pin "2") (pinfunction "A_2") (pintype "unspecified"))
      (node (ref "LED192") (pin "2") (pinfunction "A_2") (pintype "unspecified"))
      (node (ref "LED208") (pin "2") (pinfunction "A_2") (pintype "unspecified"))
      (node (ref "LED224") (pin "2") (pinfunction "A_2") (pintype "unspecified"))
      (node (ref "LED240") (pin "2") (pinfunction "A_2") (pintype "unspecified"))
      (node (ref "LED256") (pin "2") (pinfunction "A_2") (pintype "unspecified"))
      (node (ref "LED32") (pin "2") (pinfunction "A_2") (pintype "unspecified"))
      (node (ref "LED33") (pin "2") (pinfunction "A_2") (pintype "unspecified"))
      (node (ref "LED49") (pin "2") (pinfunction "A_2") (pintype "unspecified"))
      (node (ref "LED65") (pin "2") (pinfunction "A_2") (pintype "unspecified"))
      (node (ref "LED81") (pin "2") (pinfunction "A_2") (pintype "unspecified"))
      (node (ref "LED97") (pin "2") (pinfunction "A_2") (pintype "unspecified"))
    )
    (net (code "18") (name "A") (class "Default")
      (node (ref "LED145") (pin "1") (pinfunction "C_1") (pintype "unspecified"))
      (node (ref "LED146") (pin "1") (pinfunction "C_1") (pintype "unspecified"))
      (node (ref "LED147") (pin "1") (pinfunction "C_1") (pintype "unspecified"))
      (node (ref "LED148") (pin "1") (pinfunction "C_1") (pintype "unspecified"))
      (node (ref "LED149") (pin "1") (pinfunction "C_1") (pintype "unspecified"))
      (node (ref "LED150") (pin "1") (pinfunction "C_1") (pintype "unspecified"))
      (node (ref "LED151") (pin "1") (pinfunction "C_1") (pintype "unspecified"))
      (node (ref "LED152") (pin "1") (pinfunction "C_1") (pintype "unspecified"))
      (node (ref "LED153") (pin "1") (pinfunction "C_1") (pintype "unspecified"))
      (node (ref "LED154") (pin "1") (pinfunction "C_1") (pintype "unspecified"))
      (node (ref "LED155") (pin "1") (pinfunction "C_1") (pintype "unspecified"))
      (node (ref "LED156") (pin "1") (pinfunction "C_1") (pintype "unspecified"))
      (node (ref "LED157") (pin "1") (pinfunction "C_1") (pintype "unspecified"))
      (node (ref "LED158") (pin "1") (pinfunction "C_1") (pintype "unspecified"))
      (node (ref "LED159") (pin "1") (pinfunction "C_1") (pintype "unspecified"))
      (node (ref "LED160") (pin "1") (pinfunction "C_1") (pintype "unspecified"))
    )
    (net (code "19") (name "B") (class "Default")
      (node (ref "LED129") (pin "1") (pinfunction "C_1") (pintype "unspecified"))
      (node (ref "LED130") (pin "1") (pinfunction "C_1") (pintype "unspecified"))
      (node (ref "LED131") (pin "1") (pinfunction "C_1") (pintype "unspecified"))
      (node (ref "LED132") (pin "1") (pinfunction "C_1") (pintype "unspecified"))
      (node (ref "LED133") (pin "1") (pinfunction "C_1") (pintype "unspecified"))
      (node (ref "LED134") (pin "1") (pinfunction "C_1") (pintype "unspecified"))
      (node (ref "LED135") (pin "1") (pinfunction "C_1") (pintype "unspecified"))
      (node (ref "LED136") (pin "1") (pinfunction "C_1") (pintype "unspecified"))
      (node (ref "LED137") (pin "1") (pinfunction "C_1") (pintype "unspecified"))
      (node (ref "LED138") (pin "1") (pinfunction "C_1") (pintype "unspecified"))
      (node (ref "LED139") (pin "1") (pinfunction "C_1") (pintype "unspecified"))
      (node (ref "LED140") (pin "1") (pinfunction "C_1") (pintype "unspecified"))
      (node (ref "LED141") (pin "1") (pinfunction "C_1") (pintype "unspecified"))
      (node (ref "LED142") (pin "1") (pinfunction "C_1") (pintype "unspecified"))
      (node (ref "LED143") (pin "1") (pinfunction "C_1") (pintype "unspecified"))
      (node (ref "LED144") (pin "1") (pinfunction "C_1") (pintype "unspecified"))
    )
    (net (code "20") (name "C") (class "Default")
      (node (ref "LED177") (pin "1") (pinfunction "C_1") (pintype "unspecified"))
      (node (ref "LED178") (pin "1") (pinfunction "C_1") (pintype "unspecified"))
      (node (ref "LED179") (pin "1") (pinfunction "C_1") (pintype "unspecified"))
      (node (ref "LED180") (pin "1") (pinfunction "C_1") (pintype "unspecified"))
      (node (ref "LED181") (pin "1") (pinfunction "C_1") (pintype "unspecified"))
      (node (ref "LED182") (pin "1") (pinfunction "C_1") (pintype "unspecified"))
      (node (ref "LED183") (pin "1") (pinfunction "C_1") (pintype "unspecified"))
      (node (ref "LED184") (pin "1") (pinfunction "C_1") (pintype "unspecified"))
      (node (ref "LED185") (pin "1") (pinfunction "C_1") (pintype "unspecified"))
      (node (ref "LED186") (pin "1") (pinfunction "C_1") (pintype "unspecified"))
      (node (ref "LED187") (pin "1") (pinfunction "C_1") (pintype "unspecified"))
      (node (ref "LED188") (pin "1") (pinfunction "C_1") (pintype "unspecified"))
      (node (ref "LED189") (pin "1") (pinfunction "C_1") (pintype "unspecified"))
      (node (ref "LED190") (pin "1") (pinfunction "C_1") (pintype "unspecified"))
      (node (ref "LED191") (pin "1") (pinfunction "C_1") (pintype "unspecified"))
      (node (ref "LED192") (pin "1") (pinfunction "C_1") (pintype "unspecified"))
    )
    (net (code "21") (name "D") (class "Default")
      (node (ref "LED161") (pin "1") (pinfunction "C_1") (pintype "unspecified"))
      (node (ref "LED162") (pin "1") (pinfunction "C_1") (pintype "unspecified"))
      (node (ref "LED163") (pin "1") (pinfunction "C_1") (pintype "unspecified"))
      (node (ref "LED164") (pin "1") (pinfunction "C_1") (pintype "unspecified"))
      (node (ref "LED165") (pin "1") (pinfunction "C_1") (pintype "unspecified"))
      (node (ref "LED166") (pin "1") (pinfunction "C_1") (pintype "unspecified"))
      (node (ref "LED167") (pin "1") (pinfunction "C_1") (pintype "unspecified"))
      (node (ref "LED168") (pin "1") (pinfunction "C_1") (pintype "unspecified"))
      (node (ref "LED169") (pin "1") (pinfunction "C_1") (pintype "unspecified"))
      (node (ref "LED170") (pin "1") (pinfunction "C_1") (pintype "unspecified"))
      (node (ref "LED171") (pin "1") (pinfunction "C_1") (pintype "unspecified"))
      (node (ref "LED172") (pin "1") (pinfunction "C_1") (pintype "unspecified"))
      (node (ref "LED173") (pin "1") (pinfunction "C_1") (pintype "unspecified"))
      (node (ref "LED174") (pin "1") (pinfunction "C_1") (pintype "unspecified"))
      (node (ref "LED175") (pin "1") (pinfunction "C_1") (pintype "unspecified"))
      (node (ref "LED176") (pin "1") (pinfunction "C_1") (pintype "unspecified"))
    )
    (net (code "22") (name "E") (class "Default")
      (node (ref "LED209") (pin "1") (pinfunction "C_1") (pintype "unspecified"))
      (node (ref "LED210") (pin "1") (pinfunction "C_1") (pintype "unspecified"))
      (node (ref "LED211") (pin "1") (pinfunction "C_1") (pintype "unspecified"))
      (node (ref "LED212") (pin "1") (pinfunction "C_1") (pintype "unspecified"))
      (node (ref "LED213") (pin "1") (pinfunction "C_1") (pintype "unspecified"))
      (node (ref "LED214") (pin "1") (pinfunction "C_1") (pintype "unspecified"))
      (node (ref "LED215") (pin "1") (pinfunction "C_1") (pintype "unspecified"))
      (node (ref "LED216") (pin "1") (pinfunction "C_1") (pintype "unspecified"))
      (node (ref "LED217") (pin "1") (pinfunction "C_1") (pintype "unspecified"))
      (node (ref "LED218") (pin "1") (pinfunction "C_1") (pintype "unspecified"))
      (node (ref "LED219") (pin "1") (pinfunction "C_1") (pintype "unspecified"))
      (node (ref "LED220") (pin "1") (pinfunction "C_1") (pintype "unspecified"))
      (node (ref "LED221") (pin "1") (pinfunction "C_1") (pintype "unspecified"))
      (node (ref "LED222") (pin "1") (pinfunction "C_1") (pintype "unspecified"))
      (node (ref "LED223") (pin "1") (pinfunction "C_1") (pintype "unspecified"))
      (node (ref "LED224") (pin "1") (pinfunction "C_1") (pintype "unspecified"))
    )
    (net (code "23") (name "F") (class "Default")
      (node (ref "LED193") (pin "1") (pinfunction "C_1") (pintype "unspecified"))
      (node (ref "LED194") (pin "1") (pinfunction "C_1") (pintype "unspecified"))
      (node (ref "LED195") (pin "1") (pinfunction "C_1") (pintype "unspecified"))
      (node (ref "LED196") (pin "1") (pinfunction "C_1") (pintype "unspecified"))
      (node (ref "LED197") (pin "1") (pinfunction "C_1") (pintype "unspecified"))
      (node (ref "LED198") (pin "1") (pinfunction "C_1") (pintype "unspecified"))
      (node (ref "LED199") (pin "1") (pinfunction "C_1") (pintype "unspecified"))
      (node (ref "LED200") (pin "1") (pinfunction "C_1") (pintype "unspecified"))
      (node (ref "LED201") (pin "1") (pinfunction "C_1") (pintype "unspecified"))
      (node (ref "LED202") (pin "1") (pinfunction "C_1") (pintype "unspecified"))
      (node (ref "LED203") (pin "1") (pinfunction "C_1") (pintype "unspecified"))
      (node (ref "LED204") (pin "1") (pinfunction "C_1") (pintype "unspecified"))
      (node (ref "LED205") (pin "1") (pinfunction "C_1") (pintype "unspecified"))
      (node (ref "LED206") (pin "1") (pinfunction "C_1") (pintype "unspecified"))
      (node (ref "LED207") (pin "1") (pinfunction "C_1") (pintype "unspecified"))
      (node (ref "LED208") (pin "1") (pinfunction "C_1") (pintype "unspecified"))
    )
    (net (code "24") (name "G") (class "Default")
      (node (ref "LED241") (pin "1") (pinfunction "C_1") (pintype "unspecified"))
      (node (ref "LED242") (pin "1") (pinfunction "C_1") (pintype "unspecified"))
      (node (ref "LED243") (pin "1") (pinfunction "C_1") (pintype "unspecified"))
      (node (ref "LED244") (pin "1") (pinfunction "C_1") (pintype "unspecified"))
      (node (ref "LED245") (pin "1") (pinfunction "C_1") (pintype "unspecified"))
      (node (ref "LED246") (pin "1") (pinfunction "C_1") (pintype "unspecified"))
      (node (ref "LED247") (pin "1") (pinfunction "C_1") (pintype "unspecified"))
      (node (ref "LED248") (pin "1") (pinfunction "C_1") (pintype "unspecified"))
      (node (ref "LED249") (pin "1") (pinfunction "C_1") (pintype "unspecified"))
      (node (ref "LED250") (pin "1") (pinfunction "C_1") (pintype "unspecified"))
      (node (ref "LED251") (pin "1") (pinfunction "C_1") (pintype "unspecified"))
      (node (ref "LED252") (pin "1") (pinfunction "C_1") (pintype "unspecified"))
      (node (ref "LED253") (pin "1") (pinfunction "C_1") (pintype "unspecified"))
      (node (ref "LED254") (pin "1") (pinfunction "C_1") (pintype "unspecified"))
      (node (ref "LED255") (pin "1") (pinfunction "C_1") (pintype "unspecified"))
      (node (ref "LED256") (pin "1") (pinfunction "C_1") (pintype "unspecified"))
    )
    (net (code "25") (name "GND") (class "Default")
      (node (ref "C1") (pin "1") (pinfunction "1_1") (pintype "unspecified"))
      (node (ref "C2") (pin "1") (pinfunction "1_1") (pintype "unspecified"))
      (node (ref "C3") (pin "1") (pinfunction "1_1") (pintype "unspecified"))
      (node (ref "C4") (pin "1") (pinfunction "1_1") (pintype "unspecified"))
      (node (ref "R3") (pin "1") (pinfunction "1_1") (pintype "unspecified"))
      (node (ref "U1") (pin "8") (pinfunction "GND_8") (pintype "unspecified"))
      (node (ref "U2") (pin "8") (pinfunction "GND_8") (pintype "unspecified"))
      (node (ref "U3") (pin "8") (pinfunction "GND_8") (pintype "unspecified"))
    )
    (net (code "26") (name "H") (class "Default")
      (node (ref "LED225") (pin "1") (pinfunction "C_1") (pintype "unspecified"))
      (node (ref "LED226") (pin "1") (pinfunction "C_1") (pintype "unspecified"))
      (node (ref "LED227") (pin "1") (pinfunction "C_1") (pintype "unspecified"))
      (node (ref "LED228") (pin "1") (pinfunction "C_1") (pintype "unspecified"))
      (node (ref "LED229") (pin "1") (pinfunction "C_1") (pintype "unspecified"))
      (node (ref "LED230") (pin "1") (pinfunction "C_1") (pintype "unspecified"))
      (node (ref "LED231") (pin "1") (pinfunction "C_1") (pintype "unspecified"))
      (node (ref "LED232") (pin "1") (pinfunction "C_1") (pintype "unspecified"))
      (node (ref "LED233") (pin "1") (pinfunction "C_1") (pintype "unspecified"))
      (node (ref "LED234") (pin "1") (pinfunction "C_1") (pintype "unspecified"))
      (node (ref "LED235") (pin "1") (pinfunction "C_1") (pintype "unspecified"))
      (node (ref "LED236") (pin "1") (pinfunction "C_1") (pintype "unspecified"))
      (node (ref "LED237") (pin "1") (pinfunction "C_1") (pintype "unspecified"))
      (node (ref "LED238") (pin "1") (pinfunction "C_1") (pintype "unspecified"))
      (node (ref "LED239") (pin "1") (pinfunction "C_1") (pintype "unspecified"))
      (node (ref "LED240") (pin "1") (pinfunction "C_1") (pintype "unspecified"))
    )
    (net (code "27") (name "I") (class "Default")
      (node (ref "LED100") (pin "1") (pinfunction "C_1") (pintype "unspecified"))
      (node (ref "LED101") (pin "1") (pinfunction "C_1") (pintype "unspecified"))
      (node (ref "LED102") (pin "1") (pinfunction "C_1") (pintype "unspecified"))
      (node (ref "LED103") (pin "1") (pinfunction "C_1") (pintype "unspecified"))
      (node (ref "LED104") (pin "1") (pinfunction "C_1") (pintype "unspecified"))
      (node (ref "LED105") (pin "1") (pinfunction "C_1") (pintype "unspecified"))
      (node (ref "LED106") (pin "1") (pinfunction "C_1") (pintype "unspecified"))
      (node (ref "LED107") (pin "1") (pinfunction "C_1") (pintype "unspecified"))
      (node (ref "LED108") (pin "1") (pinfunction "C_1") (pintype "unspecified"))
      (node (ref "LED109") (pin "1") (pinfunction "C_1") (pintype "unspecified"))
      (node (ref "LED110") (pin "1") (pinfunction "C_1") (pintype "unspecified"))
      (node (ref "LED111") (pin "1") (pinfunction "C_1") (pintype "unspecified"))
      (node (ref "LED112") (pin "1") (pinfunction "C_1") (pintype "unspecified"))
      (node (ref "LED97") (pin "1") (pinfunction "C_1") (pintype "unspecified"))
      (node (ref "LED98") (pin "1") (pinfunction "C_1") (pintype "unspecified"))
      (node (ref "LED99") (pin "1") (pinfunction "C_1") (pintype "unspecified"))
    )
    (net (code "28") (name "J") (class "Default")
      (node (ref "LED113") (pin "1") (pinfunction "C_1") (pintype "unspecified"))
      (node (ref "LED114") (pin "1") (pinfunction "C_1") (pintype "unspecified"))
      (node (ref "LED115") (pin "1") (pinfunction "C_1") (pintype "unspecified"))
      (node (ref "LED116") (pin "1") (pinfunction "C_1") (pintype "unspecified"))
      (node (ref "LED117") (pin "1") (pinfunction "C_1") (pintype "unspecified"))
      (node (ref "LED118") (pin "1") (pinfunction "C_1") (pintype "unspecified"))
      (node (ref "LED119") (pin "1") (pinfunction "C_1") (pintype "unspecified"))
      (node (ref "LED120") (pin "1") (pinfunction "C_1") (pintype "unspecified"))
      (node (ref "LED121") (pin "1") (pinfunction "C_1") (pintype "unspecified"))
      (node (ref "LED122") (pin "1") (pinfunction "C_1") (pintype "unspecified"))
      (node (ref "LED123") (pin "1") (pinfunction "C_1") (pintype "unspecified"))
      (node (ref "LED124") (pin "1") (pinfunction "C_1") (pintype "unspecified"))
      (node (ref "LED125") (pin "1") (pinfunction "C_1") (pintype "unspecified"))
      (node (ref "LED126") (pin "1") (pinfunction "C_1") (pintype "unspecified"))
      (node (ref "LED127") (pin "1") (pinfunction "C_1") (pintype "unspecified"))
      (node (ref "LED128") (pin "1") (pinfunction "C_1") (pintype "unspecified"))
    )
    (net (code "29") (name "K") (class "Default")
      (node (ref "LED65") (pin "1") (pinfunction "C_1") (pintype "unspecified"))
      (node (ref "LED66") (pin "1") (pinfunction "C_1") (pintype "unspecified"))
      (node (ref "LED67") (pin "1") (pinfunction "C_1") (pintype "unspecified"))
      (node (ref "LED68") (pin "1") (pinfunction "C_1") (pintype "unspecified"))
      (node (ref "LED69") (pin "1") (pinfunction "C_1") (pintype "unspecified"))
      (node (ref "LED70") (pin "1") (pinfunction "C_1") (pintype "unspecified"))
      (node (ref "LED71") (pin "1") (pinfunction "C_1") (pintype "unspecified"))
      (node (ref "LED72") (pin "1") (pinfunction "C_1") (pintype "unspecified"))
      (node (ref "LED73") (pin "1") (pinfunction "C_1") (pintype "unspecified"))
      (node (ref "LED74") (pin "1") (pinfunction "C_1") (pintype "unspecified"))
      (node (ref "LED75") (pin "1") (pinfunction "C_1") (pintype "unspecified"))
      (node (ref "LED76") (pin "1") (pinfunction "C_1") (pintype "unspecified"))
      (node (ref "LED77") (pin "1") (pinfunction "C_1") (pintype "unspecified"))
      (node (ref "LED78") (pin "1") (pinfunction "C_1") (pintype "unspecified"))
      (node (ref "LED79") (pin "1") (pinfunction "C_1") (pintype "unspecified"))
      (node (ref "LED80") (pin "1") (pinfunction "C_1") (pintype "unspecified"))
    )
    (net (code "30") (name "L") (class "Default")
      (node (ref "LED81") (pin "1") (pinfunction "C_1") (pintype "unspecified"))
      (node (ref "LED82") (pin "1") (pinfunction "C_1") (pintype "unspecified"))
      (node (ref "LED83") (pin "1") (pinfunction "C_1") (pintype "unspecified"))
      (node (ref "LED84") (pin "1") (pinfunction "C_1") (pintype "unspecified"))
      (node (ref "LED85") (pin "1") (pinfunction "C_1") (pintype "unspecified"))
      (node (ref "LED86") (pin "1") (pinfunction "C_1") (pintype "unspecified"))
      (node (ref "LED87") (pin "1") (pinfunction "C_1") (pintype "unspecified"))
      (node (ref "LED88") (pin "1") (pinfunction "C_1") (pintype "unspecified"))
      (node (ref "LED89") (pin "1") (pinfunction "C_1") (pintype "unspecified"))
      (node (ref "LED90") (pin "1") (pinfunction "C_1") (pintype "unspecified"))
      (node (ref "LED91") (pin "1") (pinfunction "C_1") (pintype "unspecified"))
      (node (ref "LED92") (pin "1") (pinfunction "C_1") (pintype "unspecified"))
      (node (ref "LED93") (pin "1") (pinfunction "C_1") (pintype "unspecified"))
      (node (ref "LED94") (pin "1") (pinfunction "C_1") (pintype "unspecified"))
      (node (ref "LED95") (pin "1") (pinfunction "C_1") (pintype "unspecified"))
      (node (ref "LED96") (pin "1") (pinfunction "C_1") (pintype "unspecified"))
    )
    (net (code "31") (name "M") (class "Default")
      (node (ref "LED33") (pin "1") (pinfunction "C_1") (pintype "unspecified"))
      (node (ref "LED34") (pin "1") (pinfunction "C_1") (pintype "unspecified"))
      (node (ref "LED35") (pin "1") (pinfunction "C_1") (pintype "unspecified"))
      (node (ref "LED36") (pin "1") (pinfunction "C_1") (pintype "unspecified"))
      (node (ref "LED37") (pin "1") (pinfunction "C_1") (pintype "unspecified"))
      (node (ref "LED38") (pin "1") (pinfunction "C_1") (pintype "unspecified"))
      (node (ref "LED39") (pin "1") (pinfunction "C_1") (pintype "unspecified"))
      (node (ref "LED40") (pin "1") (pinfunction "C_1") (pintype "unspecified"))
      (node (ref "LED41") (pin "1") (pinfunction "C_1") (pintype "unspecified"))
      (node (ref "LED42") (pin "1") (pinfunction "C_1") (pintype "unspecified"))
      (node (ref "LED43") (pin "1") (pinfunction "C_1") (pintype "unspecified"))
      (node (ref "LED44") (pin "1") (pinfunction "C_1") (pintype "unspecified"))
      (node (ref "LED45") (pin "1") (pinfunction "C_1") (pintype "unspecified"))
      (node (ref "LED46") (pin "1") (pinfunction "C_1") (pintype "unspecified"))
      (node (ref "LED47") (pin "1") (pinfunction "C_1") (pintype "unspecified"))
      (node (ref "LED48") (pin "1") (pinfunction "C_1") (pintype "unspecified"))
    )
    (net (code "32") (name "N") (class "Default")
      (node (ref "LED49") (pin "1") (pinfunction "C_1") (pintype "unspecified"))
      (node (ref "LED50") (pin "1") (pinfunction "C_1") (pintype "unspecified"))
      (node (ref "LED51") (pin "1") (pinfunction "C_1") (pintype "unspecified"))
      (node (ref "LED52") (pin "1") (pinfunction "C_1") (pintype "unspecified"))
      (node (ref "LED53") (pin "1") (pinfunction "C_1") (pintype "unspecified"))
      (node (ref "LED54") (pin "1") (pinfunction "C_1") (pintype "unspecified"))
      (node (ref "LED55") (pin "1") (pinfunction "C_1") (pintype "unspecified"))
      (node (ref "LED56") (pin "1") (pinfunction "C_1") (pintype "unspecified"))
      (node (ref "LED57") (pin "1") (pinfunction "C_1") (pintype "unspecified"))
      (node (ref "LED58") (pin "1") (pinfunction "C_1") (pintype "unspecified"))
      (node (ref "LED59") (pin "1") (pinfunction "C_1") (pintype "unspecified"))
      (node (ref "LED60") (pin "1") (pinfunction "C_1") (pintype "unspecified"))
      (node (ref "LED61") (pin "1") (pinfunction "C_1") (pintype "unspecified"))
      (node (ref "LED62") (pin "1") (pinfunction "C_1") (pintype "unspecified"))
      (node (ref "LED63") (pin "1") (pinfunction "C_1") (pintype "unspecified"))
      (node (ref "LED64") (pin "1") (pinfunction "C_1") (pintype "unspecified"))
    )
    (net (code "33") (name "Net-(C4-Pad2)") (class "Default")
      (node (ref "C4") (pin "2") (pinfunction "2_2") (pintype "unspecified"))
      (node (ref "R2") (pin "1") (pinfunction "1_1") (pintype "unspecified"))
      (node (ref "X1") (pin "2") (pinfunction "2_2") (pintype "input"))
    )
    (net (code "34") (name "Net-(U1-A0)") (class "Default")
      (node (ref "U1") (pin "1") (pinfunction "A0_1") (pintype "unspecified"))
      (node (ref "U2") (pin "7") (pinfunction "Q4_7") (pintype "unspecified"))
      (node (ref "U3") (pin "1") (pinfunction "A0_1") (pintype "unspecified"))
    )
    (net (code "35") (name "Net-(U1-A1)") (class "Default")
      (node (ref "U1") (pin "2") (pinfunction "A1_2") (pintype "unspecified"))
      (node (ref "U2") (pin "5") (pinfunction "Q5_5") (pintype "unspecified"))
      (node (ref "U3") (pin "2") (pinfunction "A1_2") (pintype "unspecified"))
    )
    (net (code "36") (name "Net-(U1-A2)") (class "Default")
      (node (ref "U1") (pin "3") (pinfunction "A2_3") (pintype "unspecified"))
      (node (ref "U2") (pin "4") (pinfunction "Q6_4") (pintype "unspecified"))
      (node (ref "U3") (pin "3") (pinfunction "A2_3") (pintype "unspecified"))
    )
    (net (code "37") (name "Net-(U1-E2#)") (class "Default")
      (node (ref "U1") (pin "5") (pinfunction "E2#_5") (pintype "unspecified"))
      (node (ref "U2") (pin "6") (pinfunction "Q7_6") (pintype "unspecified"))
      (node (ref "U3") (pin "6") (pinfunction "E3_6") (pintype "unspecified"))
    )
    (net (code "38") (name "Net-(U2-MR)") (class "Default")
      (node (ref "R3") (pin "2") (pinfunction "2_2") (pintype "unspecified"))
      (node (ref "U2") (pin "12") (pinfunction "MR_12") (pintype "unspecified"))
    )
    (net (code "39") (name "Net-(U2-φI)") (class "Default")
      (node (ref "C3") (pin "2") (pinfunction "2_2") (pintype "unspecified"))
      (node (ref "R1") (pin "1") (pinfunction "1_1") (pintype "unspecified"))
      (node (ref "U2") (pin "11") (pinfunction "φI_11") (pintype "unspecified"))
      (node (ref "X1") (pin "1") (pinfunction "1_1") (pintype "input"))
    )
    (net (code "40") (name "Net-(U2-φO#)") (class "Default")
      (node (ref "R1") (pin "2") (pinfunction "2_2") (pintype "unspecified"))
      (node (ref "R2") (pin "2") (pinfunction "2_2") (pintype "unspecified"))
      (node (ref "U2") (pin "10") (pinfunction "φO#_10") (pintype "unspecified"))
    )
    (net (code "41") (name "O") (class "Default")
      (node (ref "LED17") (pin "1") (pinfunction "C_1") (pintype "unspecified"))
      (node (ref "LED18") (pin "1") (pinfunction "C_1") (pintype "unspecified"))
      (node (ref "LED19") (pin "1") (pinfunction "C_1") (pintype "unspecified"))
      (node (ref "LED20") (pin "1") (pinfunction "C_1") (pintype "unspecified"))
      (node (ref "LED21") (pin "1") (pinfunction "C_1") (pintype "unspecified"))
      (node (ref "LED22") (pin "1") (pinfunction "C_1") (pintype "unspecified"))
      (node (ref "LED23") (pin "1") (pinfunction "C_1") (pintype "unspecified"))
      (node (ref "LED24") (pin "1") (pinfunction "C_1") (pintype "unspecified"))
      (node (ref "LED25") (pin "1") (pinfunction "C_1") (pintype "unspecified"))
      (node (ref "LED26") (pin "1") (pinfunction "C_1") (pintype "unspecified"))
      (node (ref "LED27") (pin "1") (pinfunction "C_1") (pintype "unspecified"))
      (node (ref "LED28") (pin "1") (pinfunction "C_1") (pintype "unspecified"))
      (node (ref "LED29") (pin "1") (pinfunction "C_1") (pintype "unspecified"))
      (node (ref "LED30") (pin "1") (pinfunction "C_1") (pintype "unspecified"))
      (node (ref "LED31") (pin "1") (pinfunction "C_1") (pintype "unspecified"))
      (node (ref "LED32") (pin "1") (pinfunction "C_1") (pintype "unspecified"))
    )
    (net (code "42") (name "P") (class "Default")
      (node (ref "LED1") (pin "1") (pinfunction "C_1") (pintype "unspecified"))
      (node (ref "LED10") (pin "1") (pinfunction "C_1") (pintype "unspecified"))
      (node (ref "LED11") (pin "1") (pinfunction "C_1") (pintype "unspecified"))
      (node (ref "LED12") (pin "1") (pinfunction "C_1") (pintype "unspecified"))
      (node (ref "LED13") (pin "1") (pinfunction "C_1") (pintype "unspecified"))
      (node (ref "LED14") (pin "1") (pinfunction "C_1") (pintype "unspecified"))
      (node (ref "LED15") (pin "1") (pinfunction "C_1") (pintype "unspecified"))
      (node (ref "LED16") (pin "1") (pinfunction "C_1") (pintype "unspecified"))
      (node (ref "LED2") (pin "1") (pinfunction "C_1") (pintype "unspecified"))
      (node (ref "LED3") (pin "1") (pinfunction "C_1") (pintype "unspecified"))
      (node (ref "LED4") (pin "1") (pinfunction "C_1") (pintype "unspecified"))
      (node (ref "LED5") (pin "1") (pinfunction "C_1") (pintype "unspecified"))
      (node (ref "LED6") (pin "1") (pinfunction "C_1") (pintype "unspecified"))
      (node (ref "LED7") (pin "1") (pinfunction "C_1") (pintype "unspecified"))
      (node (ref "LED8") (pin "1") (pinfunction "C_1") (pintype "unspecified"))
      (node (ref "LED9") (pin "1") (pinfunction "C_1") (pintype "unspecified"))
    )
    (net (code "43") (name "unconnected-(LED1-Pad3)") (class "Default")
      (node (ref "LED1") (pin "3") (pinfunction "3_3") (pintype "unspecified"))
    )
    (net (code "44") (name "unconnected-(LED2-Pad3)") (class "Default")
      (node (ref "LED2") (pin "3") (pinfunction "3_3") (pintype "unspecified"))
    )
    (net (code "45") (name "unconnected-(LED3-Pad3)") (class "Default")
      (node (ref "LED3") (pin "3") (pinfunction "3_3") (pintype "unspecified"))
    )
    (net (code "46") (name "unconnected-(LED4-Pad3)") (class "Default")
      (node (ref "LED4") (pin "3") (pinfunction "3_3") (pintype "unspecified"))
    )
    (net (code "47") (name "unconnected-(LED5-Pad3)") (class "Default")
      (node (ref "LED5") (pin "3") (pinfunction "3_3") (pintype "unspecified"))
    )
    (net (code "48") (name "unconnected-(LED6-Pad3)") (class "Default")
      (node (ref "LED6") (pin "3") (pinfunction "3_3") (pintype "unspecified"))
    )
    (net (code "49") (name "unconnected-(LED7-Pad3)") (class "Default")
      (node (ref "LED7") (pin "3") (pinfunction "3_3") (pintype "unspecified"))
    )
    (net (code "50") (name "unconnected-(LED8-Pad3)") (class "Default")
      (node (ref "LED8") (pin "3") (pinfunction "3_3") (pintype "unspecified"))
    )
    (net (code "51") (name "unconnected-(LED9-Pad3)") (class "Default")
      (node (ref "LED9") (pin "3") (pinfunction "3_3") (pintype "unspecified"))
    )
    (net (code "52") (name "unconnected-(LED10-Pad3)") (class "Default")
      (node (ref "LED10") (pin "3") (pinfunction "3_3") (pintype "unspecified"))
    )
    (net (code "53") (name "unconnected-(LED11-Pad3)") (class "Default")
      (node (ref "LED11") (pin "3") (pinfunction "3_3") (pintype "unspecified"))
    )
    (net (code "54") (name "unconnected-(LED12-Pad3)") (class "Default")
      (node (ref "LED12") (pin "3") (pinfunction "3_3") (pintype "unspecified"))
    )
    (net (code "55") (name "unconnected-(LED13-Pad3)") (class "Default")
      (node (ref "LED13") (pin "3") (pinfunction "3_3") (pintype "unspecified"))
    )
    (net (code "56") (name "unconnected-(LED14-Pad3)") (class "Default")
      (node (ref "LED14") (pin "3") (pinfunction "3_3") (pintype "unspecified"))
    )
    (net (code "57") (name "unconnected-(LED15-Pad3)") (class "Default")
      (node (ref "LED15") (pin "3") (pinfunction "3_3") (pintype "unspecified"))
    )
    (net (code "58") (name "unconnected-(LED16-Pad3)") (class "Default")
      (node (ref "LED16") (pin "3") (pinfunction "3_3") (pintype "unspecified"))
    )
    (net (code "59") (name "unconnected-(LED17-Pad3)") (class "Default")
      (node (ref "LED17") (pin "3") (pinfunction "3_3") (pintype "unspecified"))
    )
    (net (code "60") (name "unconnected-(LED18-Pad3)") (class "Default")
      (node (ref "LED18") (pin "3") (pinfunction "3_3") (pintype "unspecified"))
    )
    (net (code "61") (name "unconnected-(LED19-Pad3)") (class "Default")
      (node (ref "LED19") (pin "3") (pinfunction "3_3") (pintype "unspecified"))
    )
    (net (code "62") (name "unconnected-(LED20-Pad3)") (class "Default")
      (node (ref "LED20") (pin "3") (pinfunction "3_3") (pintype "unspecified"))
    )
    (net (code "63") (name "unconnected-(LED21-Pad3)") (class "Default")
      (node (ref "LED21") (pin "3") (pinfunction "3_3") (pintype "unspecified"))
    )
    (net (code "64") (name "unconnected-(LED22-Pad3)") (class "Default")
      (node (ref "LED22") (pin "3") (pinfunction "3_3") (pintype "unspecified"))
    )
    (net (code "65") (name "unconnected-(LED23-Pad3)") (class "Default")
      (node (ref "LED23") (pin "3") (pinfunction "3_3") (pintype "unspecified"))
    )
    (net (code "66") (name "unconnected-(LED24-Pad3)") (class "Default")
      (node (ref "LED24") (pin "3") (pinfunction "3_3") (pintype "unspecified"))
    )
    (net (code "67") (name "unconnected-(LED25-Pad3)") (class "Default")
      (node (ref "LED25") (pin "3") (pinfunction "3_3") (pintype "unspecified"))
    )
    (net (code "68") (name "unconnected-(LED26-Pad3)") (class "Default")
      (node (ref "LED26") (pin "3") (pinfunction "3_3") (pintype "unspecified"))
    )
    (net (code "69") (name "unconnected-(LED27-Pad3)") (class "Default")
      (node (ref "LED27") (pin "3") (pinfunction "3_3") (pintype "unspecified"))
    )
    (net (code "70") (name "unconnected-(LED28-Pad3)") (class "Default")
      (node (ref "LED28") (pin "3") (pinfunction "3_3") (pintype "unspecified"))
    )
    (net (code "71") (name "unconnected-(LED29-Pad3)") (class "Default")
      (node (ref "LED29") (pin "3") (pinfunction "3_3") (pintype "unspecified"))
    )
    (net (code "72") (name "unconnected-(LED30-Pad3)") (class "Default")
      (node (ref "LED30") (pin "3") (pinfunction "3_3") (pintype "unspecified"))
    )
    (net (code "73") (name "unconnected-(LED31-Pad3)") (class "Default")
      (node (ref "LED31") (pin "3") (pinfunction "3_3") (pintype "unspecified"))
    )
    (net (code "74") (name "unconnected-(LED32-Pad3)") (class "Default")
      (node (ref "LED32") (pin "3") (pinfunction "3_3") (pintype "unspecified"))
    )
    (net (code "75") (name "unconnected-(LED33-Pad3)") (class "Default")
      (node (ref "LED33") (pin "3") (pinfunction "3_3") (pintype "unspecified"))
    )
    (net (code "76") (name "unconnected-(LED34-Pad3)") (class "Default")
      (node (ref "LED34") (pin "3") (pinfunction "3_3") (pintype "unspecified"))
    )
    (net (code "77") (name "unconnected-(LED35-Pad3)") (class "Default")
      (node (ref "LED35") (pin "3") (pinfunction "3_3") (pintype "unspecified"))
    )
    (net (code "78") (name "unconnected-(LED36-Pad3)") (class "Default")
      (node (ref "LED36") (pin "3") (pinfunction "3_3") (pintype "unspecified"))
    )
    (net (code "79") (name "unconnected-(LED37-Pad3)") (class "Default")
      (node (ref "LED37") (pin "3") (pinfunction "3_3") (pintype "unspecified"))
    )
    (net (code "80") (name "unconnected-(LED38-Pad3)") (class "Default")
      (node (ref "LED38") (pin "3") (pinfunction "3_3") (pintype "unspecified"))
    )
    (net (code "81") (name "unconnected-(LED39-Pad3)") (class "Default")
      (node (ref "LED39") (pin "3") (pinfunction "3_3") (pintype "unspecified"))
    )
    (net (code "82") (name "unconnected-(LED40-Pad3)") (class "Default")
      (node (ref "LED40") (pin "3") (pinfunction "3_3") (pintype "unspecified"))
    )
    (net (code "83") (name "unconnected-(LED41-Pad3)") (class "Default")
      (node (ref "LED41") (pin "3") (pinfunction "3_3") (pintype "unspecified"))
    )
    (net (code "84") (name "unconnected-(LED42-Pad3)") (class "Default")
      (node (ref "LED42") (pin "3") (pinfunction "3_3") (pintype "unspecified"))
    )
    (net (code "85") (name "unconnected-(LED43-Pad3)") (class "Default")
      (node (ref "LED43") (pin "3") (pinfunction "3_3") (pintype "unspecified"))
    )
    (net (code "86") (name "unconnected-(LED44-Pad3)") (class "Default")
      (node (ref "LED44") (pin "3") (pinfunction "3_3") (pintype "unspecified"))
    )
    (net (code "87") (name "unconnected-(LED45-Pad3)") (class "Default")
      (node (ref "LED45") (pin "3") (pinfunction "3_3") (pintype "unspecified"))
    )
    (net (code "88") (name "unconnected-(LED46-Pad3)") (class "Default")
      (node (ref "LED46") (pin "3") (pinfunction "3_3") (pintype "unspecified"))
    )
    (net (code "89") (name "unconnected-(LED47-Pad3)") (class "Default")
      (node (ref "LED47") (pin "3") (pinfunction "3_3") (pintype "unspecified"))
    )
    (net (code "90") (name "unconnected-(LED48-Pad3)") (class "Default")
      (node (ref "LED48") (pin "3") (pinfunction "3_3") (pintype "unspecified"))
    )
    (net (code "91") (name "unconnected-(LED49-Pad3)") (class "Default")
      (node (ref "LED49") (pin "3") (pinfunction "3_3") (pintype "unspecified"))
    )
    (net (code "92") (name "unconnected-(LED50-Pad3)") (class "Default")
      (node (ref "LED50") (pin "3") (pinfunction "3_3") (pintype "unspecified"))
    )
    (net (code "93") (name "unconnected-(LED51-Pad3)") (class "Default")
      (node (ref "LED51") (pin "3") (pinfunction "3_3") (pintype "unspecified"))
    )
    (net (code "94") (name "unconnected-(LED52-Pad3)") (class "Default")
      (node (ref "LED52") (pin "3") (pinfunction "3_3") (pintype "unspecified"))
    )
    (net (code "95") (name "unconnected-(LED53-Pad3)") (class "Default")
      (node (ref "LED53") (pin "3") (pinfunction "3_3") (pintype "unspecified"))
    )
    (net (code "96") (name "unconnected-(LED54-Pad3)") (class "Default")
      (node (ref "LED54") (pin "3") (pinfunction "3_3") (pintype "unspecified"))
    )
    (net (code "97") (name "unconnected-(LED55-Pad3)") (class "Default")
      (node (ref "LED55") (pin "3") (pinfunction "3_3") (pintype "unspecified"))
    )
    (net (code "98") (name "unconnected-(LED56-Pad3)") (class "Default")
      (node (ref "LED56") (pin "3") (pinfunction "3_3") (pintype "unspecified"))
    )
    (net (code "99") (name "unconnected-(LED57-Pad3)") (class "Default")
      (node (ref "LED57") (pin "3") (pinfunction "3_3") (pintype "unspecified"))
    )
    (net (code "100") (name "unconnected-(LED58-Pad3)") (class "Default")
      (node (ref "LED58") (pin "3") (pinfunction "3_3") (pintype "unspecified"))
    )
    (net (code "101") (name "unconnected-(LED59-Pad3)") (class "Default")
      (node (ref "LED59") (pin "3") (pinfunction "3_3") (pintype "unspecified"))
    )
    (net (code "102") (name "unconnected-(LED60-Pad3)") (class "Default")
      (node (ref "LED60") (pin "3") (pinfunction "3_3") (pintype "unspecified"))
    )
    (net (code "103") (name "unconnected-(LED61-Pad3)") (class "Default")
      (node (ref "LED61") (pin "3") (pinfunction "3_3") (pintype "unspecified"))
    )
    (net (code "104") (name "unconnected-(LED62-Pad3)") (class "Default")
      (node (ref "LED62") (pin "3") (pinfunction "3_3") (pintype "unspecified"))
    )
    (net (code "105") (name "unconnected-(LED63-Pad3)") (class "Default")
      (node (ref "LED63") (pin "3") (pinfunction "3_3") (pintype "unspecified"))
    )
    (net (code "106") (name "unconnected-(LED64-Pad3)") (class "Default")
      (node (ref "LED64") (pin "3") (pinfunction "3_3") (pintype "unspecified"))
    )
    (net (code "107") (name "unconnected-(LED65-Pad3)") (class "Default")
      (node (ref "LED65") (pin "3") (pinfunction "3_3") (pintype "unspecified"))
    )
    (net (code "108") (name "unconnected-(LED66-Pad3)") (class "Default")
      (node (ref "LED66") (pin "3") (pinfunction "3_3") (pintype "unspecified"))
    )
    (net (code "109") (name "unconnected-(LED67-Pad3)") (class "Default")
      (node (ref "LED67") (pin "3") (pinfunction "3_3") (pintype "unspecified"))
    )
    (net (code "110") (name "unconnected-(LED68-Pad3)") (class "Default")
      (node (ref "LED68") (pin "3") (pinfunction "3_3") (pintype "unspecified"))
    )
    (net (code "111") (name "unconnected-(LED69-Pad3)") (class "Default")
      (node (ref "LED69") (pin "3") (pinfunction "3_3") (pintype "unspecified"))
    )
    (net (code "112") (name "unconnected-(LED70-Pad3)") (class "Default")
      (node (ref "LED70") (pin "3") (pinfunction "3_3") (pintype "unspecified"))
    )
    (net (code "113") (name "unconnected-(LED71-Pad3)") (class "Default")
      (node (ref "LED71") (pin "3") (pinfunction "3_3") (pintype "unspecified"))
    )
    (net (code "114") (name "unconnected-(LED72-Pad3)") (class "Default")
      (node (ref "LED72") (pin "3") (pinfunction "3_3") (pintype "unspecified"))
    )
    (net (code "115") (name "unconnected-(LED73-Pad3)") (class "Default")
      (node (ref "LED73") (pin "3") (pinfunction "3_3") (pintype "unspecified"))
    )
    (net (code "116") (name "unconnected-(LED74-Pad3)") (class "Default")
      (node (ref "LED74") (pin "3") (pinfunction "3_3") (pintype "unspecified"))
    )
    (net (code "117") (name "unconnected-(LED75-Pad3)") (class "Default")
      (node (ref "LED75") (pin "3") (pinfunction "3_3") (pintype "unspecified"))
    )
    (net (code "118") (name "unconnected-(LED76-Pad3)") (class "Default")
      (node (ref "LED76") (pin "3") (pinfunction "3_3") (pintype "unspecified"))
    )
    (net (code "119") (name "unconnected-(LED77-Pad3)") (class "Default")
      (node (ref "LED77") (pin "3") (pinfunction "3_3") (pintype "unspecified"))
    )
    (net (code "120") (name "unconnected-(LED78-Pad3)") (class "Default")
      (node (ref "LED78") (pin "3") (pinfunction "3_3") (pintype "unspecified"))
    )
    (net (code "121") (name "unconnected-(LED79-Pad3)") (class "Default")
      (node (ref "LED79") (pin "3") (pinfunction "3_3") (pintype "unspecified"))
    )
    (net (code "122") (name "unconnected-(LED80-Pad3)") (class "Default")
      (node (ref "LED80") (pin "3") (pinfunction "3_3") (pintype "unspecified"))
    )
    (net (code "123") (name "unconnected-(LED81-Pad3)") (class "Default")
      (node (ref "LED81") (pin "3") (pinfunction "3_3") (pintype "unspecified"))
    )
    (net (code "124") (name "unconnected-(LED82-Pad3)") (class "Default")
      (node (ref "LED82") (pin "3") (pinfunction "3_3") (pintype "unspecified"))
    )
    (net (code "125") (name "unconnected-(LED83-Pad3)") (class "Default")
      (node (ref "LED83") (pin "3") (pinfunction "3_3") (pintype "unspecified"))
    )
    (net (code "126") (name "unconnected-(LED84-Pad3)") (class "Default")
      (node (ref "LED84") (pin "3") (pinfunction "3_3") (pintype "unspecified"))
    )
    (net (code "127") (name "unconnected-(LED85-Pad3)") (class "Default")
      (node (ref "LED85") (pin "3") (pinfunction "3_3") (pintype "unspecified"))
    )
    (net (code "128") (name "unconnected-(LED86-Pad3)") (class "Default")
      (node (ref "LED86") (pin "3") (pinfunction "3_3") (pintype "unspecified"))
    )
    (net (code "129") (name "unconnected-(LED87-Pad3)") (class "Default")
      (node (ref "LED87") (pin "3") (pinfunction "3_3") (pintype "unspecified"))
    )
    (net (code "130") (name "unconnected-(LED88-Pad3)") (class "Default")
      (node (ref "LED88") (pin "3") (pinfunction "3_3") (pintype "unspecified"))
    )
    (net (code "131") (name "unconnected-(LED89-Pad3)") (class "Default")
      (node (ref "LED89") (pin "3") (pinfunction "3_3") (pintype "unspecified"))
    )
    (net (code "132") (name "unconnected-(LED90-Pad3)") (class "Default")
      (node (ref "LED90") (pin "3") (pinfunction "3_3") (pintype "unspecified"))
    )
    (net (code "133") (name "unconnected-(LED91-Pad3)") (class "Default")
      (node (ref "LED91") (pin "3") (pinfunction "3_3") (pintype "unspecified"))
    )
    (net (code "134") (name "unconnected-(LED92-Pad3)") (class "Default")
      (node (ref "LED92") (pin "3") (pinfunction "3_3") (pintype "unspecified"))
    )
    (net (code "135") (name "unconnected-(LED93-Pad3)") (class "Default")
      (node (ref "LED93") (pin "3") (pinfunction "3_3") (pintype "unspecified"))
    )
    (net (code "136") (name "unconnected-(LED94-Pad3)") (class "Default")
      (node (ref "LED94") (pin "3") (pinfunction "3_3") (pintype "unspecified"))
    )
    (net (code "137") (name "unconnected-(LED95-Pad3)") (class "Default")
      (node (ref "LED95") (pin "3") (pinfunction "3_3") (pintype "unspecified"))
    )
    (net (code "138") (name "unconnected-(LED96-Pad3)") (class "Default")
      (node (ref "LED96") (pin "3") (pinfunction "3_3") (pintype "unspecified"))
    )
    (net (code "139") (name "unconnected-(LED97-Pad3)") (class "Default")
      (node (ref "LED97") (pin "3") (pinfunction "3_3") (pintype "unspecified"))
    )
    (net (code "140") (name "unconnected-(LED98-Pad3)") (class "Default")
      (node (ref "LED98") (pin "3") (pinfunction "3_3") (pintype "unspecified"))
    )
    (net (code "141") (name "unconnected-(LED99-Pad3)") (class "Default")
      (node (ref "LED99") (pin "3") (pinfunction "3_3") (pintype "unspecified"))
    )
    (net (code "142") (name "unconnected-(LED100-Pad3)") (class "Default")
      (node (ref "LED100") (pin "3") (pinfunction "3_3") (pintype "unspecified"))
    )
    (net (code "143") (name "unconnected-(LED101-Pad3)") (class "Default")
      (node (ref "LED101") (pin "3") (pinfunction "3_3") (pintype "unspecified"))
    )
    (net (code "144") (name "unconnected-(LED102-Pad3)") (class "Default")
      (node (ref "LED102") (pin "3") (pinfunction "3_3") (pintype "unspecified"))
    )
    (net (code "145") (name "unconnected-(LED103-Pad3)") (class "Default")
      (node (ref "LED103") (pin "3") (pinfunction "3_3") (pintype "unspecified"))
    )
    (net (code "146") (name "unconnected-(LED104-Pad3)") (class "Default")
      (node (ref "LED104") (pin "3") (pinfunction "3_3") (pintype "unspecified"))
    )
    (net (code "147") (name "unconnected-(LED105-Pad3)") (class "Default")
      (node (ref "LED105") (pin "3") (pinfunction "3_3") (pintype "unspecified"))
    )
    (net (code "148") (name "unconnected-(LED106-Pad3)") (class "Default")
      (node (ref "LED106") (pin "3") (pinfunction "3_3") (pintype "unspecified"))
    )
    (net (code "149") (name "unconnected-(LED107-Pad3)") (class "Default")
      (node (ref "LED107") (pin "3") (pinfunction "3_3") (pintype "unspecified"))
    )
    (net (code "150") (name "unconnected-(LED108-Pad3)") (class "Default")
      (node (ref "LED108") (pin "3") (pinfunction "3_3") (pintype "unspecified"))
    )
    (net (code "151") (name "unconnected-(LED109-Pad3)") (class "Default")
      (node (ref "LED109") (pin "3") (pinfunction "3_3") (pintype "unspecified"))
    )
    (net (code "152") (name "unconnected-(LED110-Pad3)") (class "Default")
      (node (ref "LED110") (pin "3") (pinfunction "3_3") (pintype "unspecified"))
    )
    (net (code "153") (name "unconnected-(LED111-Pad3)") (class "Default")
      (node (ref "LED111") (pin "3") (pinfunction "3_3") (pintype "unspecified"))
    )
    (net (code "154") (name "unconnected-(LED112-Pad3)") (class "Default")
      (node (ref "LED112") (pin "3") (pinfunction "3_3") (pintype "unspecified"))
    )
    (net (code "155") (name "unconnected-(LED113-Pad3)") (class "Default")
      (node (ref "LED113") (pin "3") (pinfunction "3_3") (pintype "unspecified"))
    )
    (net (code "156") (name "unconnected-(LED114-Pad3)") (class "Default")
      (node (ref "LED114") (pin "3") (pinfunction "3_3") (pintype "unspecified"))
    )
    (net (code "157") (name "unconnected-(LED115-Pad3)") (class "Default")
      (node (ref "LED115") (pin "3") (pinfunction "3_3") (pintype "unspecified"))
    )
    (net (code "158") (name "unconnected-(LED116-Pad3)") (class "Default")
      (node (ref "LED116") (pin "3") (pinfunction "3_3") (pintype "unspecified"))
    )
    (net (code "159") (name "unconnected-(LED117-Pad3)") (class "Default")
      (node (ref "LED117") (pin "3") (pinfunction "3_3") (pintype "unspecified"))
    )
    (net (code "160") (name "unconnected-(LED118-Pad3)") (class "Default")
      (node (ref "LED118") (pin "3") (pinfunction "3_3") (pintype "unspecified"))
    )
    (net (code "161") (name "unconnected-(LED119-Pad3)") (class "Default")
      (node (ref "LED119") (pin "3") (pinfunction "3_3") (pintype "unspecified"))
    )
    (net (code "162") (name "unconnected-(LED120-Pad3)") (class "Default")
      (node (ref "LED120") (pin "3") (pinfunction "3_3") (pintype "unspecified"))
    )
    (net (code "163") (name "unconnected-(LED121-Pad3)") (class "Default")
      (node (ref "LED121") (pin "3") (pinfunction "3_3") (pintype "unspecified"))
    )
    (net (code "164") (name "unconnected-(LED122-Pad3)") (class "Default")
      (node (ref "LED122") (pin "3") (pinfunction "3_3") (pintype "unspecified"))
    )
    (net (code "165") (name "unconnected-(LED123-Pad3)") (class "Default")
      (node (ref "LED123") (pin "3") (pinfunction "3_3") (pintype "unspecified"))
    )
    (net (code "166") (name "unconnected-(LED124-Pad3)") (class "Default")
      (node (ref "LED124") (pin "3") (pinfunction "3_3") (pintype "unspecified"))
    )
    (net (code "167") (name "unconnected-(LED125-Pad3)") (class "Default")
      (node (ref "LED125") (pin "3") (pinfunction "3_3") (pintype "unspecified"))
    )
    (net (code "168") (name "unconnected-(LED126-Pad3)") (class "Default")
      (node (ref "LED126") (pin "3") (pinfunction "3_3") (pintype "unspecified"))
    )
    (net (code "169") (name "unconnected-(LED127-Pad3)") (class "Default")
      (node (ref "LED127") (pin "3") (pinfunction "3_3") (pintype "unspecified"))
    )
    (net (code "170") (name "unconnected-(LED128-Pad3)") (class "Default")
      (node (ref "LED128") (pin "3") (pinfunction "3_3") (pintype "unspecified"))
    )
    (net (code "171") (name "unconnected-(LED129-Pad3)") (class "Default")
      (node (ref "LED129") (pin "3") (pinfunction "3_3") (pintype "unspecified"))
    )
    (net (code "172") (name "unconnected-(LED130-Pad3)") (class "Default")
      (node (ref "LED130") (pin "3") (pinfunction "3_3") (pintype "unspecified"))
    )
    (net (code "173") (name "unconnected-(LED131-Pad3)") (class "Default")
      (node (ref "LED131") (pin "3") (pinfunction "3_3") (pintype "unspecified"))
    )
    (net (code "174") (name "unconnected-(LED132-Pad3)") (class "Default")
      (node (ref "LED132") (pin "3") (pinfunction "3_3") (pintype "unspecified"))
    )
    (net (code "175") (name "unconnected-(LED133-Pad3)") (class "Default")
      (node (ref "LED133") (pin "3") (pinfunction "3_3") (pintype "unspecified"))
    )
    (net (code "176") (name "unconnected-(LED134-Pad3)") (class "Default")
      (node (ref "LED134") (pin "3") (pinfunction "3_3") (pintype "unspecified"))
    )
    (net (code "177") (name "unconnected-(LED135-Pad3)") (class "Default")
      (node (ref "LED135") (pin "3") (pinfunction "3_3") (pintype "unspecified"))
    )
    (net (code "178") (name "unconnected-(LED136-Pad3)") (class "Default")
      (node (ref "LED136") (pin "3") (pinfunction "3_3") (pintype "unspecified"))
    )
    (net (code "179") (name "unconnected-(LED137-Pad3)") (class "Default")
      (node (ref "LED137") (pin "3") (pinfunction "3_3") (pintype "unspecified"))
    )
    (net (code "180") (name "unconnected-(LED138-Pad3)") (class "Default")
      (node (ref "LED138") (pin "3") (pinfunction "3_3") (pintype "unspecified"))
    )
    (net (code "181") (name "unconnected-(LED139-Pad3)") (class "Default")
      (node (ref "LED139") (pin "3") (pinfunction "3_3") (pintype "unspecified"))
    )
    (net (code "182") (name "unconnected-(LED140-Pad3)") (class "Default")
      (node (ref "LED140") (pin "3") (pinfunction "3_3") (pintype "unspecified"))
    )
    (net (code "183") (name "unconnected-(LED141-Pad3)") (class "Default")
      (node (ref "LED141") (pin "3") (pinfunction "3_3") (pintype "unspecified"))
    )
    (net (code "184") (name "unconnected-(LED142-Pad3)") (class "Default")
      (node (ref "LED142") (pin "3") (pinfunction "3_3") (pintype "unspecified"))
    )
    (net (code "185") (name "unconnected-(LED143-Pad3)") (class "Default")
      (node (ref "LED143") (pin "3") (pinfunction "3_3") (pintype "unspecified"))
    )
    (net (code "186") (name "unconnected-(LED144-Pad3)") (class "Default")
      (node (ref "LED144") (pin "3") (pinfunction "3_3") (pintype "unspecified"))
    )
    (net (code "187") (name "unconnected-(LED145-Pad3)") (class "Default")
      (node (ref "LED145") (pin "3") (pinfunction "3_3") (pintype "unspecified"))
    )
    (net (code "188") (name "unconnected-(LED146-Pad3)") (class "Default")
      (node (ref "LED146") (pin "3") (pinfunction "3_3") (pintype "unspecified"))
    )
    (net (code "189") (name "unconnected-(LED147-Pad3)") (class "Default")
      (node (ref "LED147") (pin "3") (pinfunction "3_3") (pintype "unspecified"))
    )
    (net (code "190") (name "unconnected-(LED148-Pad3)") (class "Default")
      (node (ref "LED148") (pin "3") (pinfunction "3_3") (pintype "unspecified"))
    )
    (net (code "191") (name "unconnected-(LED149-Pad3)") (class "Default")
      (node (ref "LED149") (pin "3") (pinfunction "3_3") (pintype "unspecified"))
    )
    (net (code "192") (name "unconnected-(LED150-Pad3)") (class "Default")
      (node (ref "LED150") (pin "3") (pinfunction "3_3") (pintype "unspecified"))
    )
    (net (code "193") (name "unconnected-(LED151-Pad3)") (class "Default")
      (node (ref "LED151") (pin "3") (pinfunction "3_3") (pintype "unspecified"))
    )
    (net (code "194") (name "unconnected-(LED152-Pad3)") (class "Default")
      (node (ref "LED152") (pin "3") (pinfunction "3_3") (pintype "unspecified"))
    )
    (net (code "195") (name "unconnected-(LED153-Pad3)") (class "Default")
      (node (ref "LED153") (pin "3") (pinfunction "3_3") (pintype "unspecified"))
    )
    (net (code "196") (name "unconnected-(LED154-Pad3)") (class "Default")
      (node (ref "LED154") (pin "3") (pinfunction "3_3") (pintype "unspecified"))
    )
    (net (code "197") (name "unconnected-(LED155-Pad3)") (class "Default")
      (node (ref "LED155") (pin "3") (pinfunction "3_3") (pintype "unspecified"))
    )
    (net (code "198") (name "unconnected-(LED156-Pad3)") (class "Default")
      (node (ref "LED156") (pin "3") (pinfunction "3_3") (pintype "unspecified"))
    )
    (net (code "199") (name "unconnected-(LED157-Pad3)") (class "Default")
      (node (ref "LED157") (pin "3") (pinfunction "3_3") (pintype "unspecified"))
    )
    (net (code "200") (name "unconnected-(LED158-Pad3)") (class "Default")
      (node (ref "LED158") (pin "3") (pinfunction "3_3") (pintype "unspecified"))
    )
    (net (code "201") (name "unconnected-(LED159-Pad3)") (class "Default")
      (node (ref "LED159") (pin "3") (pinfunction "3_3") (pintype "unspecified"))
    )
    (net (code "202") (name "unconnected-(LED160-Pad3)") (class "Default")
      (node (ref "LED160") (pin "3") (pinfunction "3_3") (pintype "unspecified"))
    )
    (net (code "203") (name "unconnected-(LED161-Pad3)") (class "Default")
      (node (ref "LED161") (pin "3") (pinfunction "3_3") (pintype "unspecified"))
    )
    (net (code "204") (name "unconnected-(LED162-Pad3)") (class "Default")
      (node (ref "LED162") (pin "3") (pinfunction "3_3") (pintype "unspecified"))
    )
    (net (code "205") (name "unconnected-(LED163-Pad3)") (class "Default")
      (node (ref "LED163") (pin "3") (pinfunction "3_3") (pintype "unspecified"))
    )
    (net (code "206") (name "unconnected-(LED164-Pad3)") (class "Default")
      (node (ref "LED164") (pin "3") (pinfunction "3_3") (pintype "unspecified"))
    )
    (net (code "207") (name "unconnected-(LED165-Pad3)") (class "Default")
      (node (ref "LED165") (pin "3") (pinfunction "3_3") (pintype "unspecified"))
    )
    (net (code "208") (name "unconnected-(LED166-Pad3)") (class "Default")
      (node (ref "LED166") (pin "3") (pinfunction "3_3") (pintype "unspecified"))
    )
    (net (code "209") (name "unconnected-(LED167-Pad3)") (class "Default")
      (node (ref "LED167") (pin "3") (pinfunction "3_3") (pintype "unspecified"))
    )
    (net (code "210") (name "unconnected-(LED168-Pad3)") (class "Default")
      (node (ref "LED168") (pin "3") (pinfunction "3_3") (pintype "unspecified"))
    )
    (net (code "211") (name "unconnected-(LED169-Pad3)") (class "Default")
      (node (ref "LED169") (pin "3") (pinfunction "3_3") (pintype "unspecified"))
    )
    (net (code "212") (name "unconnected-(LED170-Pad3)") (class "Default")
      (node (ref "LED170") (pin "3") (pinfunction "3_3") (pintype "unspecified"))
    )
    (net (code "213") (name "unconnected-(LED171-Pad3)") (class "Default")
      (node (ref "LED171") (pin "3") (pinfunction "3_3") (pintype "unspecified"))
    )
    (net (code "214") (name "unconnected-(LED172-Pad3)") (class "Default")
      (node (ref "LED172") (pin "3") (pinfunction "3_3") (pintype "unspecified"))
    )
    (net (code "215") (name "unconnected-(LED173-Pad3)") (class "Default")
      (node (ref "LED173") (pin "3") (pinfunction "3_3") (pintype "unspecified"))
    )
    (net (code "216") (name "unconnected-(LED174-Pad3)") (class "Default")
      (node (ref "LED174") (pin "3") (pinfunction "3_3") (pintype "unspecified"))
    )
    (net (code "217") (name "unconnected-(LED175-Pad3)") (class "Default")
      (node (ref "LED175") (pin "3") (pinfunction "3_3") (pintype "unspecified"))
    )
    (net (code "218") (name "unconnected-(LED176-Pad3)") (class "Default")
      (node (ref "LED176") (pin "3") (pinfunction "3_3") (pintype "unspecified"))
    )
    (net (code "219") (name "unconnected-(LED177-Pad3)") (class "Default")
      (node (ref "LED177") (pin "3") (pinfunction "3_3") (pintype "unspecified"))
    )
    (net (code "220") (name "unconnected-(LED178-Pad3)") (class "Default")
      (node (ref "LED178") (pin "3") (pinfunction "3_3") (pintype "unspecified"))
    )
    (net (code "221") (name "unconnected-(LED179-Pad3)") (class "Default")
      (node (ref "LED179") (pin "3") (pinfunction "3_3") (pintype "unspecified"))
    )
    (net (code "222") (name "unconnected-(LED180-Pad3)") (class "Default")
      (node (ref "LED180") (pin "3") (pinfunction "3_3") (pintype "unspecified"))
    )
    (net (code "223") (name "unconnected-(LED181-Pad3)") (class "Default")
      (node (ref "LED181") (pin "3") (pinfunction "3_3") (pintype "unspecified"))
    )
    (net (code "224") (name "unconnected-(LED182-Pad3)") (class "Default")
      (node (ref "LED182") (pin "3") (pinfunction "3_3") (pintype "unspecified"))
    )
    (net (code "225") (name "unconnected-(LED183-Pad3)") (class "Default")
      (node (ref "LED183") (pin "3") (pinfunction "3_3") (pintype "unspecified"))
    )
    (net (code "226") (name "unconnected-(LED184-Pad3)") (class "Default")
      (node (ref "LED184") (pin "3") (pinfunction "3_3") (pintype "unspecified"))
    )
    (net (code "227") (name "unconnected-(LED185-Pad3)") (class "Default")
      (node (ref "LED185") (pin "3") (pinfunction "3_3") (pintype "unspecified"))
    )
    (net (code "228") (name "unconnected-(LED186-Pad3)") (class "Default")
      (node (ref "LED186") (pin "3") (pinfunction "3_3") (pintype "unspecified"))
    )
    (net (code "229") (name "unconnected-(LED187-Pad3)") (class "Default")
      (node (ref "LED187") (pin "3") (pinfunction "3_3") (pintype "unspecified"))
    )
    (net (code "230") (name "unconnected-(LED188-Pad3)") (class "Default")
      (node (ref "LED188") (pin "3") (pinfunction "3_3") (pintype "unspecified"))
    )
    (net (code "231") (name "unconnected-(LED189-Pad3)") (class "Default")
      (node (ref "LED189") (pin "3") (pinfunction "3_3") (pintype "unspecified"))
    )
    (net (code "232") (name "unconnected-(LED190-Pad3)") (class "Default")
      (node (ref "LED190") (pin "3") (pinfunction "3_3") (pintype "unspecified"))
    )
    (net (code "233") (name "unconnected-(LED191-Pad3)") (class "Default")
      (node (ref "LED191") (pin "3") (pinfunction "3_3") (pintype "unspecified"))
    )
    (net (code "234") (name "unconnected-(LED192-Pad3)") (class "Default")
      (node (ref "LED192") (pin "3") (pinfunction "3_3") (pintype "unspecified"))
    )
    (net (code "235") (name "unconnected-(LED193-Pad3)") (class "Default")
      (node (ref "LED193") (pin "3") (pinfunction "3_3") (pintype "unspecified"))
    )
    (net (code "236") (name "unconnected-(LED194-Pad3)") (class "Default")
      (node (ref "LED194") (pin "3") (pinfunction "3_3") (pintype "unspecified"))
    )
    (net (code "237") (name "unconnected-(LED195-Pad3)") (class "Default")
      (node (ref "LED195") (pin "3") (pinfunction "3_3") (pintype "unspecified"))
    )
    (net (code "238") (name "unconnected-(LED196-Pad3)") (class "Default")
      (node (ref "LED196") (pin "3") (pinfunction "3_3") (pintype "unspecified"))
    )
    (net (code "239") (name "unconnected-(LED197-Pad3)") (class "Default")
      (node (ref "LED197") (pin "3") (pinfunction "3_3") (pintype "unspecified"))
    )
    (net (code "240") (name "unconnected-(LED198-Pad3)") (class "Default")
      (node (ref "LED198") (pin "3") (pinfunction "3_3") (pintype "unspecified"))
    )
    (net (code "241") (name "unconnected-(LED199-Pad3)") (class "Default")
      (node (ref "LED199") (pin "3") (pinfunction "3_3") (pintype "unspecified"))
    )
    (net (code "242") (name "unconnected-(LED200-Pad3)") (class "Default")
      (node (ref "LED200") (pin "3") (pinfunction "3_3") (pintype "unspecified"))
    )
    (net (code "243") (name "unconnected-(LED201-Pad3)") (class "Default")
      (node (ref "LED201") (pin "3") (pinfunction "3_3") (pintype "unspecified"))
    )
    (net (code "244") (name "unconnected-(LED202-Pad3)") (class "Default")
      (node (ref "LED202") (pin "3") (pinfunction "3_3") (pintype "unspecified"))
    )
    (net (code "245") (name "unconnected-(LED203-Pad3)") (class "Default")
      (node (ref "LED203") (pin "3") (pinfunction "3_3") (pintype "unspecified"))
    )
    (net (code "246") (name "unconnected-(LED204-Pad3)") (class "Default")
      (node (ref "LED204") (pin "3") (pinfunction "3_3") (pintype "unspecified"))
    )
    (net (code "247") (name "unconnected-(LED205-Pad3)") (class "Default")
      (node (ref "LED205") (pin "3") (pinfunction "3_3") (pintype "unspecified"))
    )
    (net (code "248") (name "unconnected-(LED206-Pad3)") (class "Default")
      (node (ref "LED206") (pin "3") (pinfunction "3_3") (pintype "unspecified"))
    )
    (net (code "249") (name "unconnected-(LED207-Pad3)") (class "Default")
      (node (ref "LED207") (pin "3") (pinfunction "3_3") (pintype "unspecified"))
    )
    (net (code "250") (name "unconnected-(LED208-Pad3)") (class "Default")
      (node (ref "LED208") (pin "3") (pinfunction "3_3") (pintype "unspecified"))
    )
    (net (code "251") (name "unconnected-(LED209-Pad3)") (class "Default")
      (node (ref "LED209") (pin "3") (pinfunction "3_3") (pintype "unspecified"))
    )
    (net (code "252") (name "unconnected-(LED210-Pad3)") (class "Default")
      (node (ref "LED210") (pin "3") (pinfunction "3_3") (pintype "unspecified"))
    )
    (net (code "253") (name "unconnected-(LED211-Pad3)") (class "Default")
      (node (ref "LED211") (pin "3") (pinfunction "3_3") (pintype "unspecified"))
    )
    (net (code "254") (name "unconnected-(LED212-Pad3)") (class "Default")
      (node (ref "LED212") (pin "3") (pinfunction "3_3") (pintype "unspecified"))
    )
    (net (code "255") (name "unconnected-(LED213-Pad3)") (class "Default")
      (node (ref "LED213") (pin "3") (pinfunction "3_3") (pintype "unspecified"))
    )
    (net (code "256") (name "unconnected-(LED214-Pad3)") (class "Default")
      (node (ref "LED214") (pin "3") (pinfunction "3_3") (pintype "unspecified"))
    )
    (net (code "257") (name "unconnected-(LED215-Pad3)") (class "Default")
      (node (ref "LED215") (pin "3") (pinfunction "3_3") (pintype "unspecified"))
    )
    (net (code "258") (name "unconnected-(LED216-Pad3)") (class "Default")
      (node (ref "LED216") (pin "3") (pinfunction "3_3") (pintype "unspecified"))
    )
    (net (code "259") (name "unconnected-(LED217-Pad3)") (class "Default")
      (node (ref "LED217") (pin "3") (pinfunction "3_3") (pintype "unspecified"))
    )
    (net (code "260") (name "unconnected-(LED218-Pad3)") (class "Default")
      (node (ref "LED218") (pin "3") (pinfunction "3_3") (pintype "unspecified"))
    )
    (net (code "261") (name "unconnected-(LED219-Pad3)") (class "Default")
      (node (ref "LED219") (pin "3") (pinfunction "3_3") (pintype "unspecified"))
    )
    (net (code "262") (name "unconnected-(LED220-Pad3)") (class "Default")
      (node (ref "LED220") (pin "3") (pinfunction "3_3") (pintype "unspecified"))
    )
    (net (code "263") (name "unconnected-(LED221-Pad3)") (class "Default")
      (node (ref "LED221") (pin "3") (pinfunction "3_3") (pintype "unspecified"))
    )
    (net (code "264") (name "unconnected-(LED222-Pad3)") (class "Default")
      (node (ref "LED222") (pin "3") (pinfunction "3_3") (pintype "unspecified"))
    )
    (net (code "265") (name "unconnected-(LED223-Pad3)") (class "Default")
      (node (ref "LED223") (pin "3") (pinfunction "3_3") (pintype "unspecified"))
    )
    (net (code "266") (name "unconnected-(LED224-Pad3)") (class "Default")
      (node (ref "LED224") (pin "3") (pinfunction "3_3") (pintype "unspecified"))
    )
    (net (code "267") (name "unconnected-(LED225-Pad3)") (class "Default")
      (node (ref "LED225") (pin "3") (pinfunction "3_3") (pintype "unspecified"))
    )
    (net (code "268") (name "unconnected-(LED226-Pad3)") (class "Default")
      (node (ref "LED226") (pin "3") (pinfunction "3_3") (pintype "unspecified"))
    )
    (net (code "269") (name "unconnected-(LED227-Pad3)") (class "Default")
      (node (ref "LED227") (pin "3") (pinfunction "3_3") (pintype "unspecified"))
    )
    (net (code "270") (name "unconnected-(LED228-Pad3)") (class "Default")
      (node (ref "LED228") (pin "3") (pinfunction "3_3") (pintype "unspecified"))
    )
    (net (code "271") (name "unconnected-(LED229-Pad3)") (class "Default")
      (node (ref "LED229") (pin "3") (pinfunction "3_3") (pintype "unspecified"))
    )
    (net (code "272") (name "unconnected-(LED230-Pad3)") (class "Default")
      (node (ref "LED230") (pin "3") (pinfunction "3_3") (pintype "unspecified"))
    )
    (net (code "273") (name "unconnected-(LED231-Pad3)") (class "Default")
      (node (ref "LED231") (pin "3") (pinfunction "3_3") (pintype "unspecified"))
    )
    (net (code "274") (name "unconnected-(LED232-Pad3)") (class "Default")
      (node (ref "LED232") (pin "3") (pinfunction "3_3") (pintype "unspecified"))
    )
    (net (code "275") (name "unconnected-(LED233-Pad3)") (class "Default")
      (node (ref "LED233") (pin "3") (pinfunction "3_3") (pintype "unspecified"))
    )
    (net (code "276") (name "unconnected-(LED234-Pad3)") (class "Default")
      (node (ref "LED234") (pin "3") (pinfunction "3_3") (pintype "unspecified"))
    )
    (net (code "277") (name "unconnected-(LED235-Pad3)") (class "Default")
      (node (ref "LED235") (pin "3") (pinfunction "3_3") (pintype "unspecified"))
    )
    (net (code "278") (name "unconnected-(LED236-Pad3)") (class "Default")
      (node (ref "LED236") (pin "3") (pinfunction "3_3") (pintype "unspecified"))
    )
    (net (code "279") (name "unconnected-(LED237-Pad3)") (class "Default")
      (node (ref "LED237") (pin "3") (pinfunction "3_3") (pintype "unspecified"))
    )
    (net (code "280") (name "unconnected-(LED238-Pad3)") (class "Default")
      (node (ref "LED238") (pin "3") (pinfunction "3_3") (pintype "unspecified"))
    )
    (net (code "281") (name "unconnected-(LED239-Pad3)") (class "Default")
      (node (ref "LED239") (pin "3") (pinfunction "3_3") (pintype "unspecified"))
    )
    (net (code "282") (name "unconnected-(LED240-Pad3)") (class "Default")
      (node (ref "LED240") (pin "3") (pinfunction "3_3") (pintype "unspecified"))
    )
    (net (code "283") (name "unconnected-(LED241-Pad3)") (class "Default")
      (node (ref "LED241") (pin "3") (pinfunction "3_3") (pintype "unspecified"))
    )
    (net (code "284") (name "unconnected-(LED242-Pad3)") (class "Default")
      (node (ref "LED242") (pin "3") (pinfunction "3_3") (pintype "unspecified"))
    )
    (net (code "285") (name "unconnected-(LED243-Pad3)") (class "Default")
      (node (ref "LED243") (pin "3") (pinfunction "3_3") (pintype "unspecified"))
    )
    (net (code "286") (name "unconnected-(LED244-Pad3)") (class "Default")
      (node (ref "LED244") (pin "3") (pinfunction "3_3") (pintype "unspecified"))
    )
    (net (code "287") (name "unconnected-(LED245-Pad3)") (class "Default")
      (node (ref "LED245") (pin "3") (pinfunction "3_3") (pintype "unspecified"))
    )
    (net (code "288") (name "unconnected-(LED246-Pad3)") (class "Default")
      (node (ref "LED246") (pin "3") (pinfunction "3_3") (pintype "unspecified"))
    )
    (net (code "289") (name "unconnected-(LED247-Pad3)") (class "Default")
      (node (ref "LED247") (pin "3") (pinfunction "3_3") (pintype "unspecified"))
    )
    (net (code "290") (name "unconnected-(LED248-Pad3)") (class "Default")
      (node (ref "LED248") (pin "3") (pinfunction "3_3") (pintype "unspecified"))
    )
    (net (code "291") (name "unconnected-(LED249-Pad3)") (class "Default")
      (node (ref "LED249") (pin "3") (pinfunction "3_3") (pintype "unspecified"))
    )
    (net (code "292") (name "unconnected-(LED250-Pad3)") (class "Default")
      (node (ref "LED250") (pin "3") (pinfunction "3_3") (pintype "unspecified"))
    )
    (net (code "293") (name "unconnected-(LED251-Pad3)") (class "Default")
      (node (ref "LED251") (pin "3") (pinfunction "3_3") (pintype "unspecified"))
    )
    (net (code "294") (name "unconnected-(LED252-Pad3)") (class "Default")
      (node (ref "LED252") (pin "3") (pinfunction "3_3") (pintype "unspecified"))
    )
    (net (code "295") (name "unconnected-(LED253-Pad3)") (class "Default")
      (node (ref "LED253") (pin "3") (pinfunction "3_3") (pintype "unspecified"))
    )
    (net (code "296") (name "unconnected-(LED254-Pad3)") (class "Default")
      (node (ref "LED254") (pin "3") (pinfunction "3_3") (pintype "unspecified"))
    )
    (net (code "297") (name "unconnected-(LED255-Pad3)") (class "Default")
      (node (ref "LED255") (pin "3") (pinfunction "3_3") (pintype "unspecified"))
    )
    (net (code "298") (name "unconnected-(LED256-Pad3)") (class "Default")
      (node (ref "LED256") (pin "3") (pinfunction "3_3") (pintype "unspecified"))
    )
    (net (code "299") (name "unconnected-(U1-E1#-Pad4)") (class "Default")
      (node (ref "U1") (pin "4") (pinfunction "E1#_4") (pintype "unspecified"))
    )
    (net (code "300") (name "unconnected-(U1-E3-Pad6)") (class "Default")
      (node (ref "U1") (pin "6") (pinfunction "E3_6") (pintype "unspecified"))
    )
    (net (code "301") (name "unconnected-(U1-Y0-Pad15)") (class "Default")
      (node (ref "U1") (pin "15") (pinfunction "Y0_15") (pintype "unspecified"))
    )
    (net (code "302") (name "unconnected-(U1-Y1-Pad14)") (class "Default")
      (node (ref "U1") (pin "14") (pinfunction "Y1_14") (pintype "unspecified"))
    )
    (net (code "303") (name "unconnected-(U1-Y2-Pad13)") (class "Default")
      (node (ref "U1") (pin "13") (pinfunction "Y2_13") (pintype "unspecified"))
    )
    (net (code "304") (name "unconnected-(U1-Y3-Pad12)") (class "Default")
      (node (ref "U1") (pin "12") (pinfunction "Y3_12") (pintype "unspecified"))
    )
    (net (code "305") (name "unconnected-(U1-Y4-Pad11)") (class "Default")
      (node (ref "U1") (pin "11") (pinfunction "Y4_11") (pintype "unspecified"))
    )
    (net (code "306") (name "unconnected-(U1-Y5-Pad10)") (class "Default")
      (node (ref "U1") (pin "10") (pinfunction "Y5_10") (pintype "unspecified"))
    )
    (net (code "307") (name "unconnected-(U1-Y6-Pad9)") (class "Default")
      (node (ref "U1") (pin "9") (pinfunction "Y6_9") (pintype "unspecified"))
    )
    (net (code "308") (name "unconnected-(U1-Y7-Pad7)") (class "Default")
      (node (ref "U1") (pin "7") (pinfunction "Y7_7") (pintype "unspecified"))
    )
    (net (code "309") (name "unconnected-(U2-Q8-Pad14)") (class "Default")
      (node (ref "U2") (pin "14") (pinfunction "Q8_14") (pintype "unspecified"))
    )
    (net (code "310") (name "unconnected-(U2-Q9-Pad13)") (class "Default")
      (node (ref "U2") (pin "13") (pinfunction "Q9_13") (pintype "unspecified"))
    )
    (net (code "311") (name "unconnected-(U2-Q10-Pad15)") (class "Default")
      (node (ref "U2") (pin "15") (pinfunction "Q10_15") (pintype "unspecified"))
    )
    (net (code "312") (name "unconnected-(U2-Q12-Pad1)") (class "Default")
      (node (ref "U2") (pin "1") (pinfunction "Q12_1") (pintype "unspecified"))
    )
    (net (code "313") (name "unconnected-(U2-Q13-Pad2)") (class "Default")
      (node (ref "U2") (pin "2") (pinfunction "Q13_2") (pintype "unspecified"))
    )
    (net (code "314") (name "unconnected-(U2-Q14-Pad3)") (class "Default")
      (node (ref "U2") (pin "3") (pinfunction "Q14_3") (pintype "unspecified"))
    )
    (net (code "315") (name "unconnected-(U2-φO-Pad9)") (class "Default")
      (node (ref "U2") (pin "9") (pinfunction "φO_9") (pintype "unspecified"))
    )
    (net (code "316") (name "unconnected-(U3-E1#-Pad4)") (class "Default")
      (node (ref "U3") (pin "4") (pinfunction "E1#_4") (pintype "unspecified"))
    )
    (net (code "317") (name "unconnected-(U3-E2#-Pad5)") (class "Default")
      (node (ref "U3") (pin "5") (pinfunction "E2#_5") (pintype "unspecified"))
    )
    (net (code "318") (name "unconnected-(U3-Y0-Pad15)") (class "Default")
      (node (ref "U3") (pin "15") (pinfunction "Y0_15") (pintype "unspecified"))
    )
    (net (code "319") (name "unconnected-(U3-Y1-Pad14)") (class "Default")
      (node (ref "U3") (pin "14") (pinfunction "Y1_14") (pintype "unspecified"))
    )
    (net (code "320") (name "unconnected-(U3-Y2-Pad13)") (class "Default")
      (node (ref "U3") (pin "13") (pinfunction "Y2_13") (pintype "unspecified"))
    )
    (net (code "321") (name "unconnected-(U3-Y3-Pad12)") (class "Default")
      (node (ref "U3") (pin "12") (pinfunction "Y3_12") (pintype "unspecified"))
    )
    (net (code "322") (name "unconnected-(U3-Y4-Pad11)") (class "Default")
      (node (ref "U3") (pin "11") (pinfunction "Y4_11") (pintype "unspecified"))
    )
    (net (code "323") (name "unconnected-(U3-Y5-Pad10)") (class "Default")
      (node (ref "U3") (pin "10") (pinfunction "Y5_10") (pintype "unspecified"))
    )
    (net (code "324") (name "unconnected-(U3-Y6-Pad9)") (class "Default")
      (node (ref "U3") (pin "9") (pinfunction "Y6_9") (pintype "unspecified"))
    )
    (net (code "325") (name "unconnected-(U3-Y7-Pad7)") (class "Default")
      (node (ref "U3") (pin "7") (pinfunction "Y7_7") (pintype "unspecified"))
    )
  )
)
